# M7106C.net
KiCad netlist of a schematic drawn in EAGLE
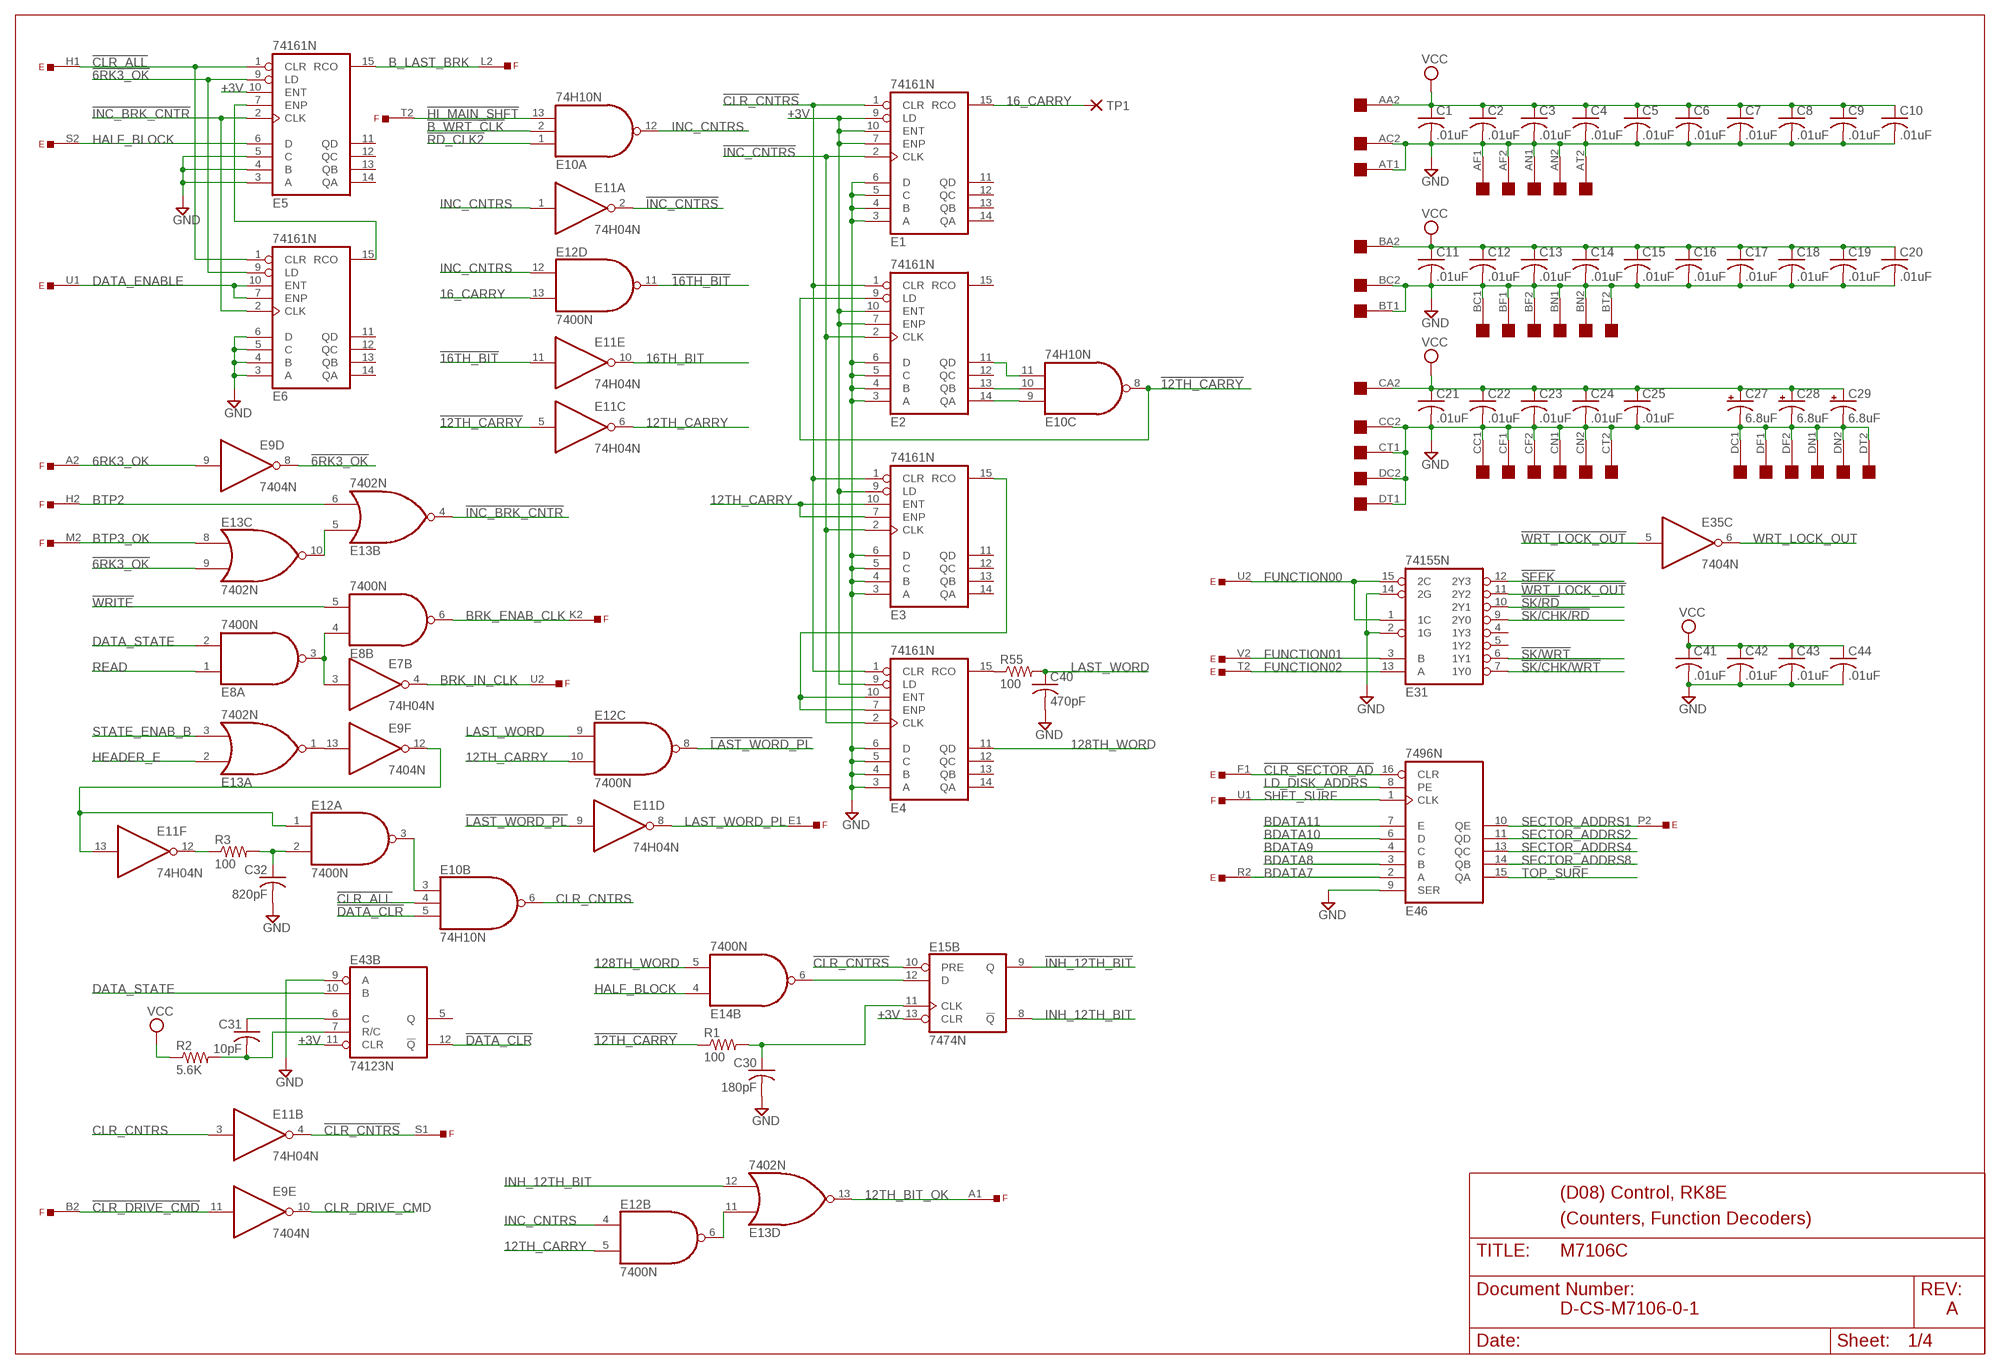
[diagram p0: schematic, sheet 1]
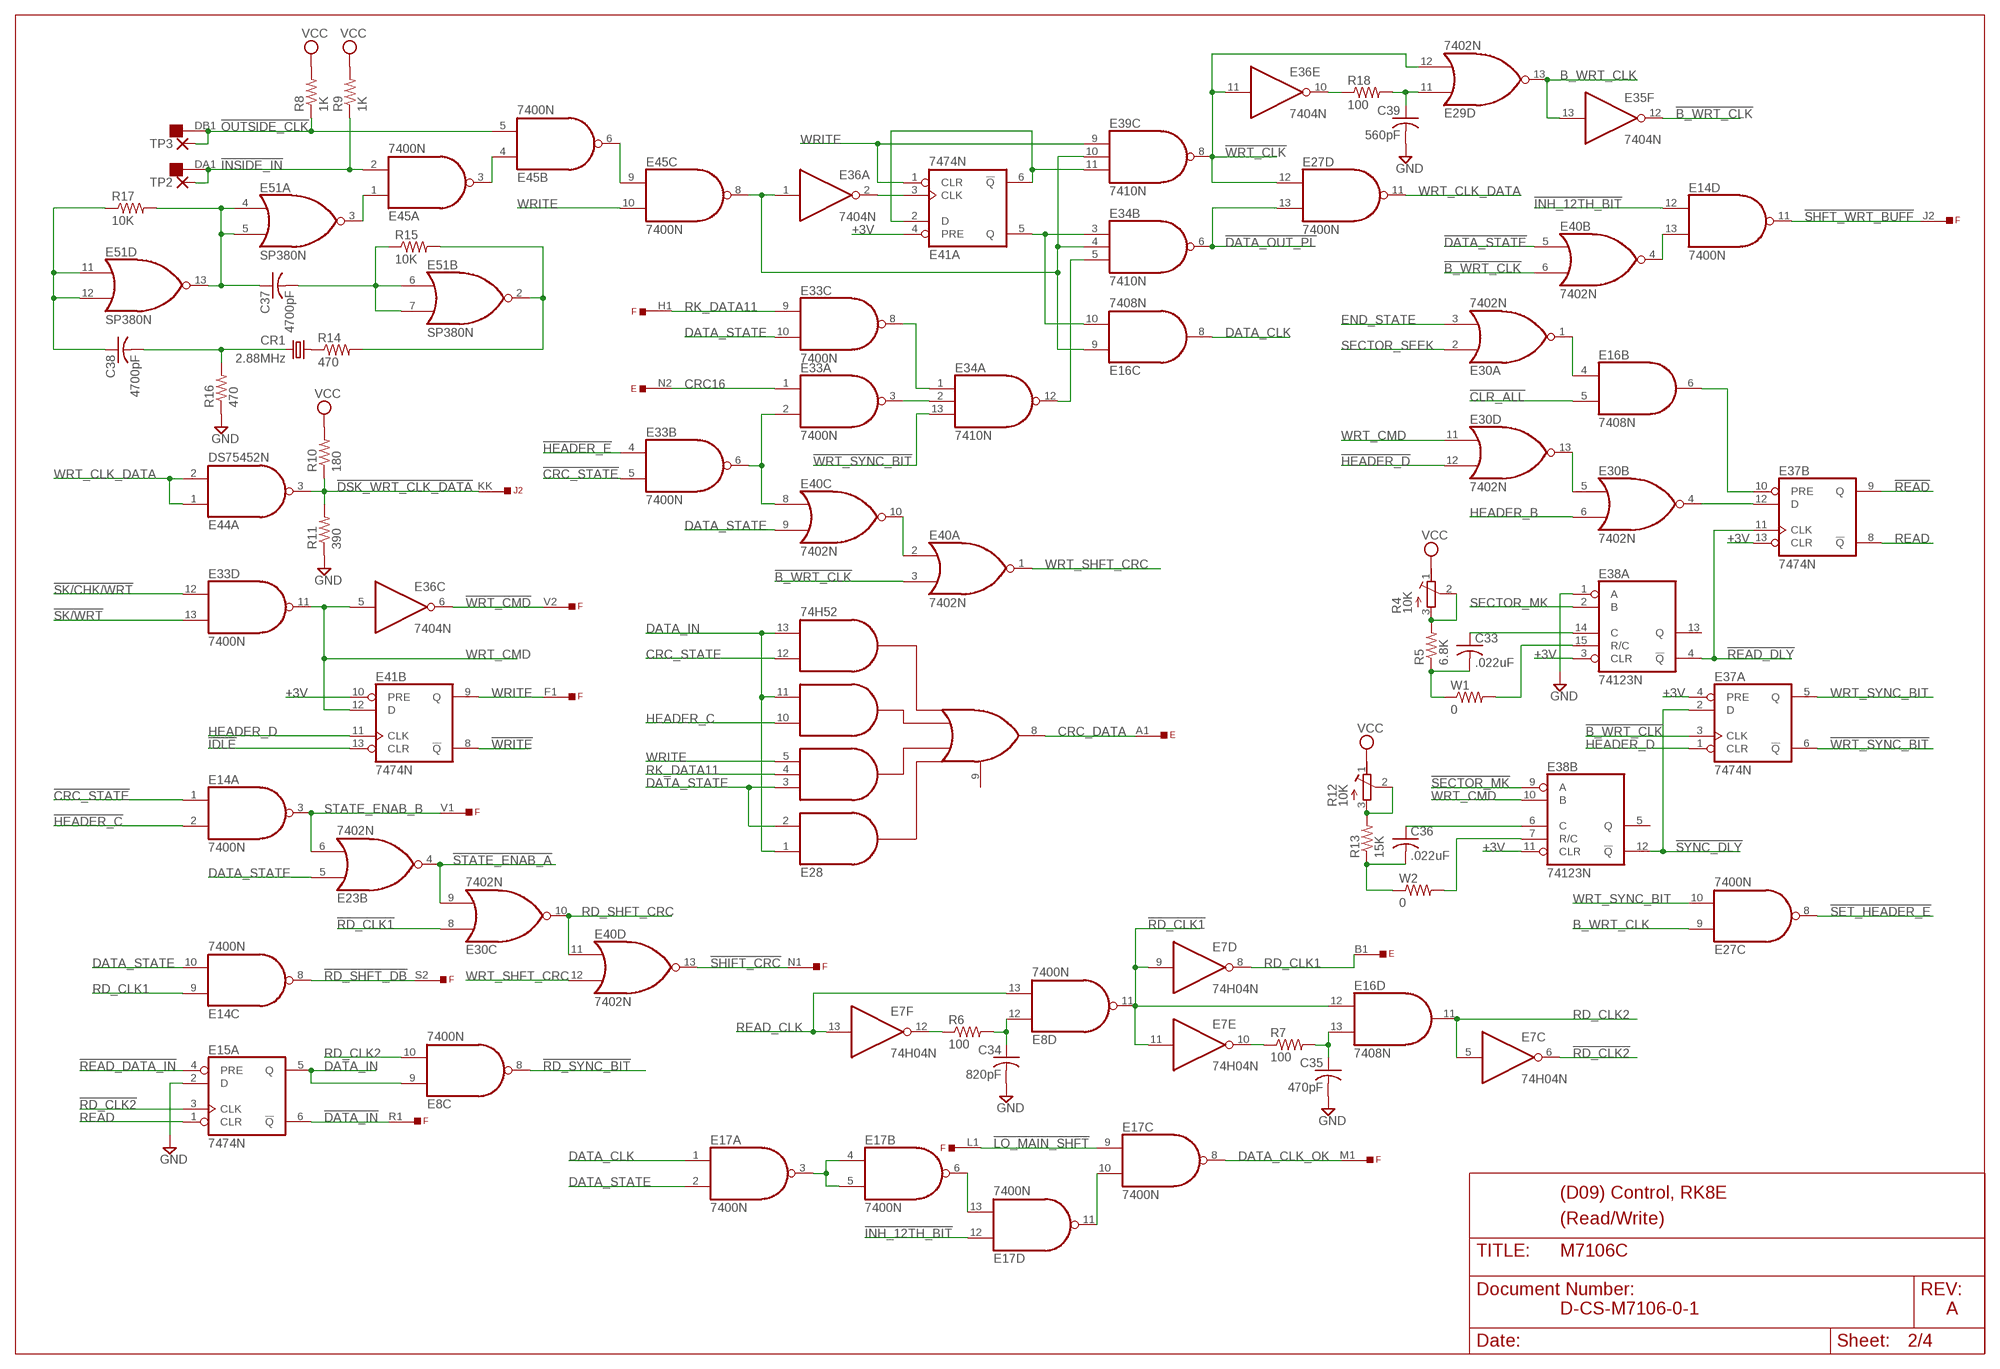
[diagram p1: schematic, sheet 2]
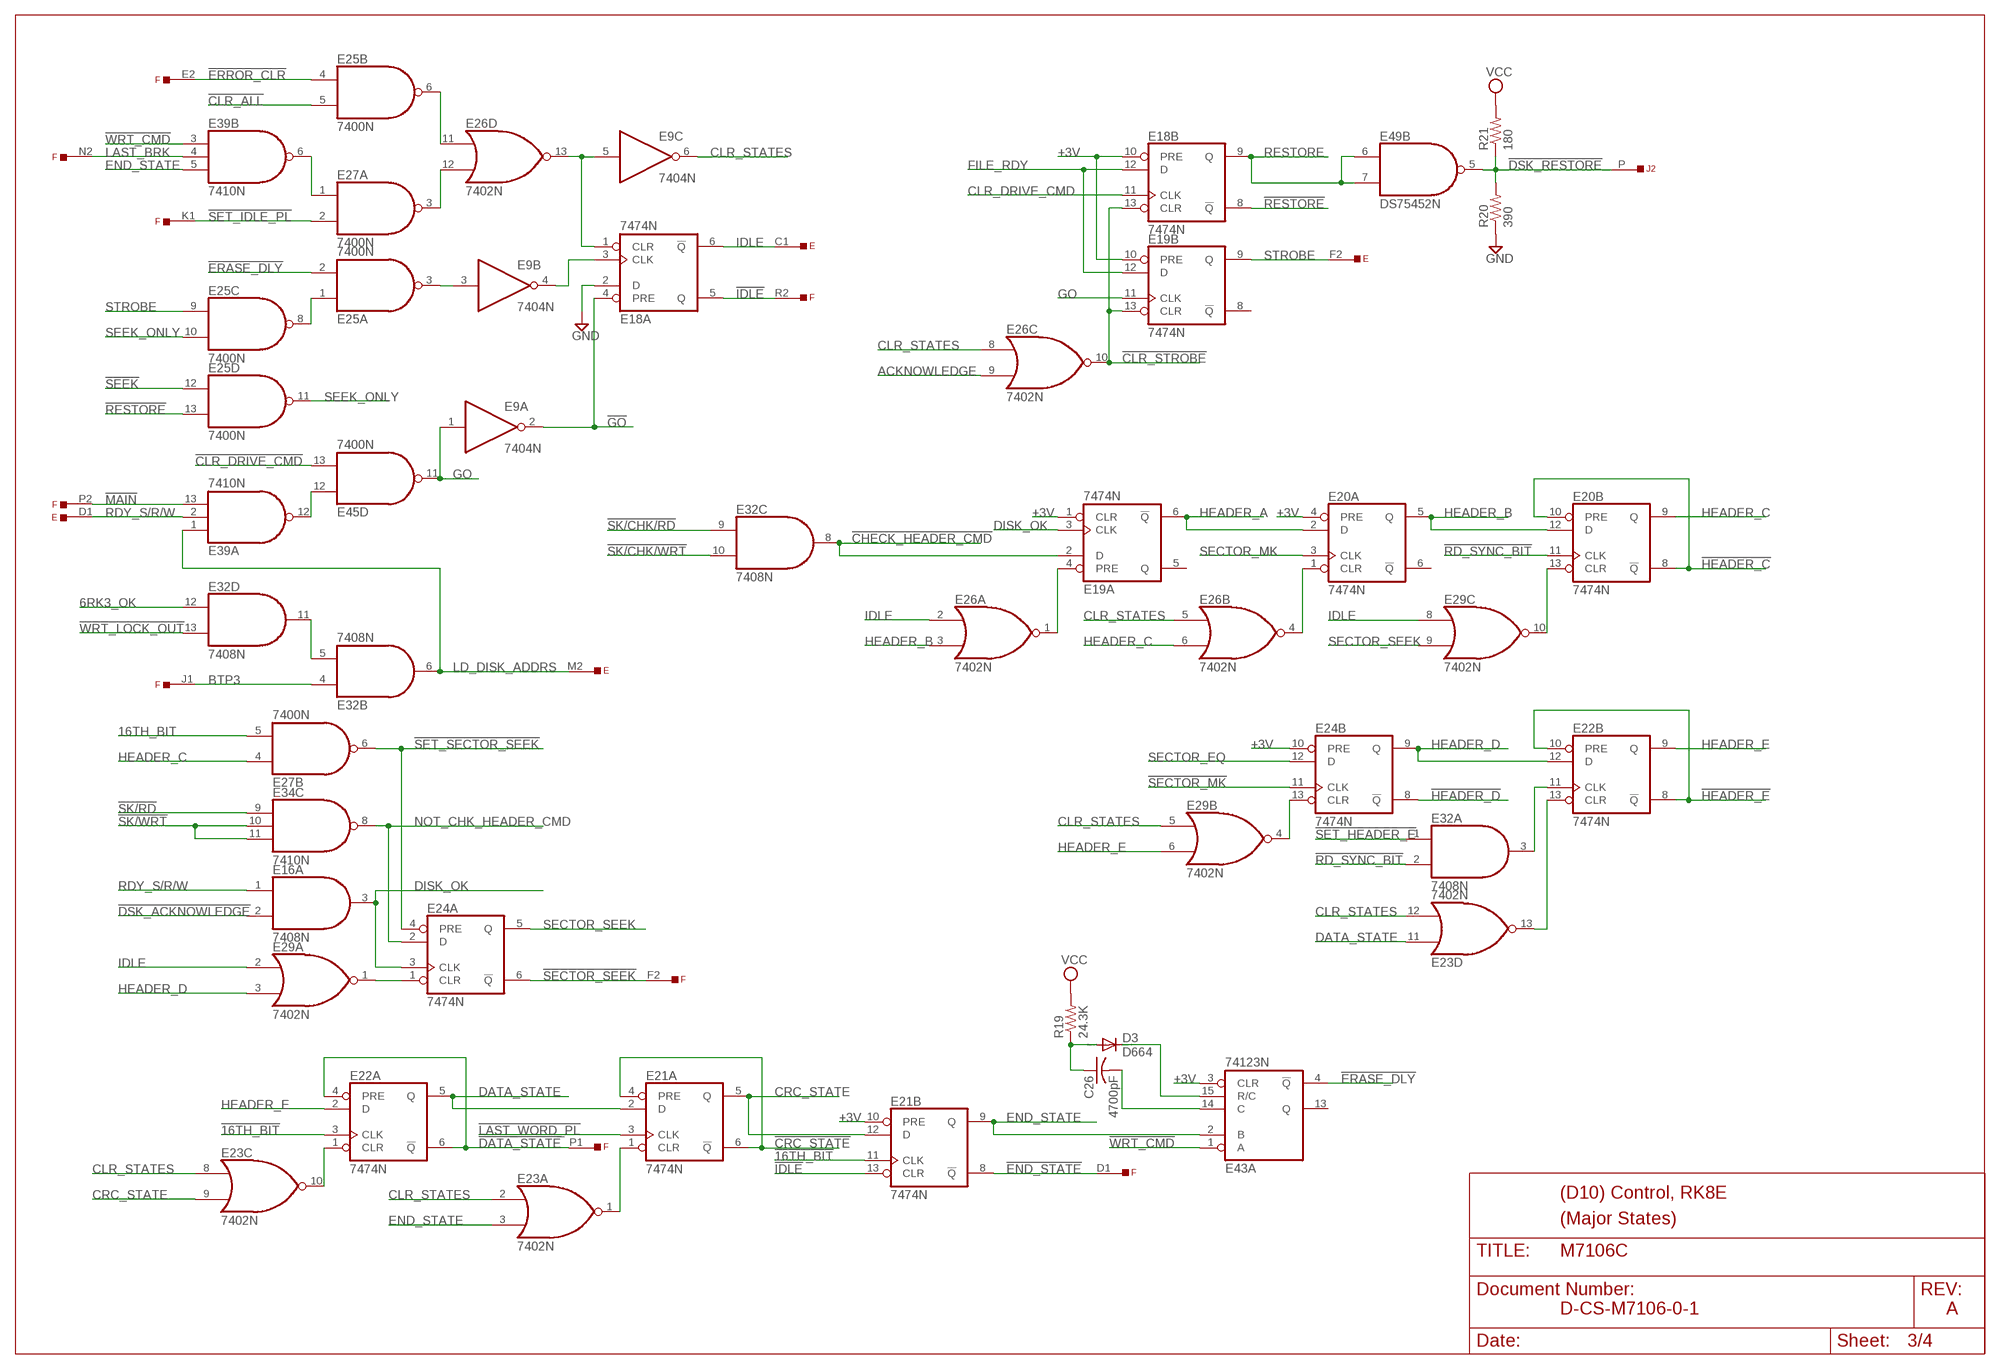
[diagram p2: schematic, sheet 3]
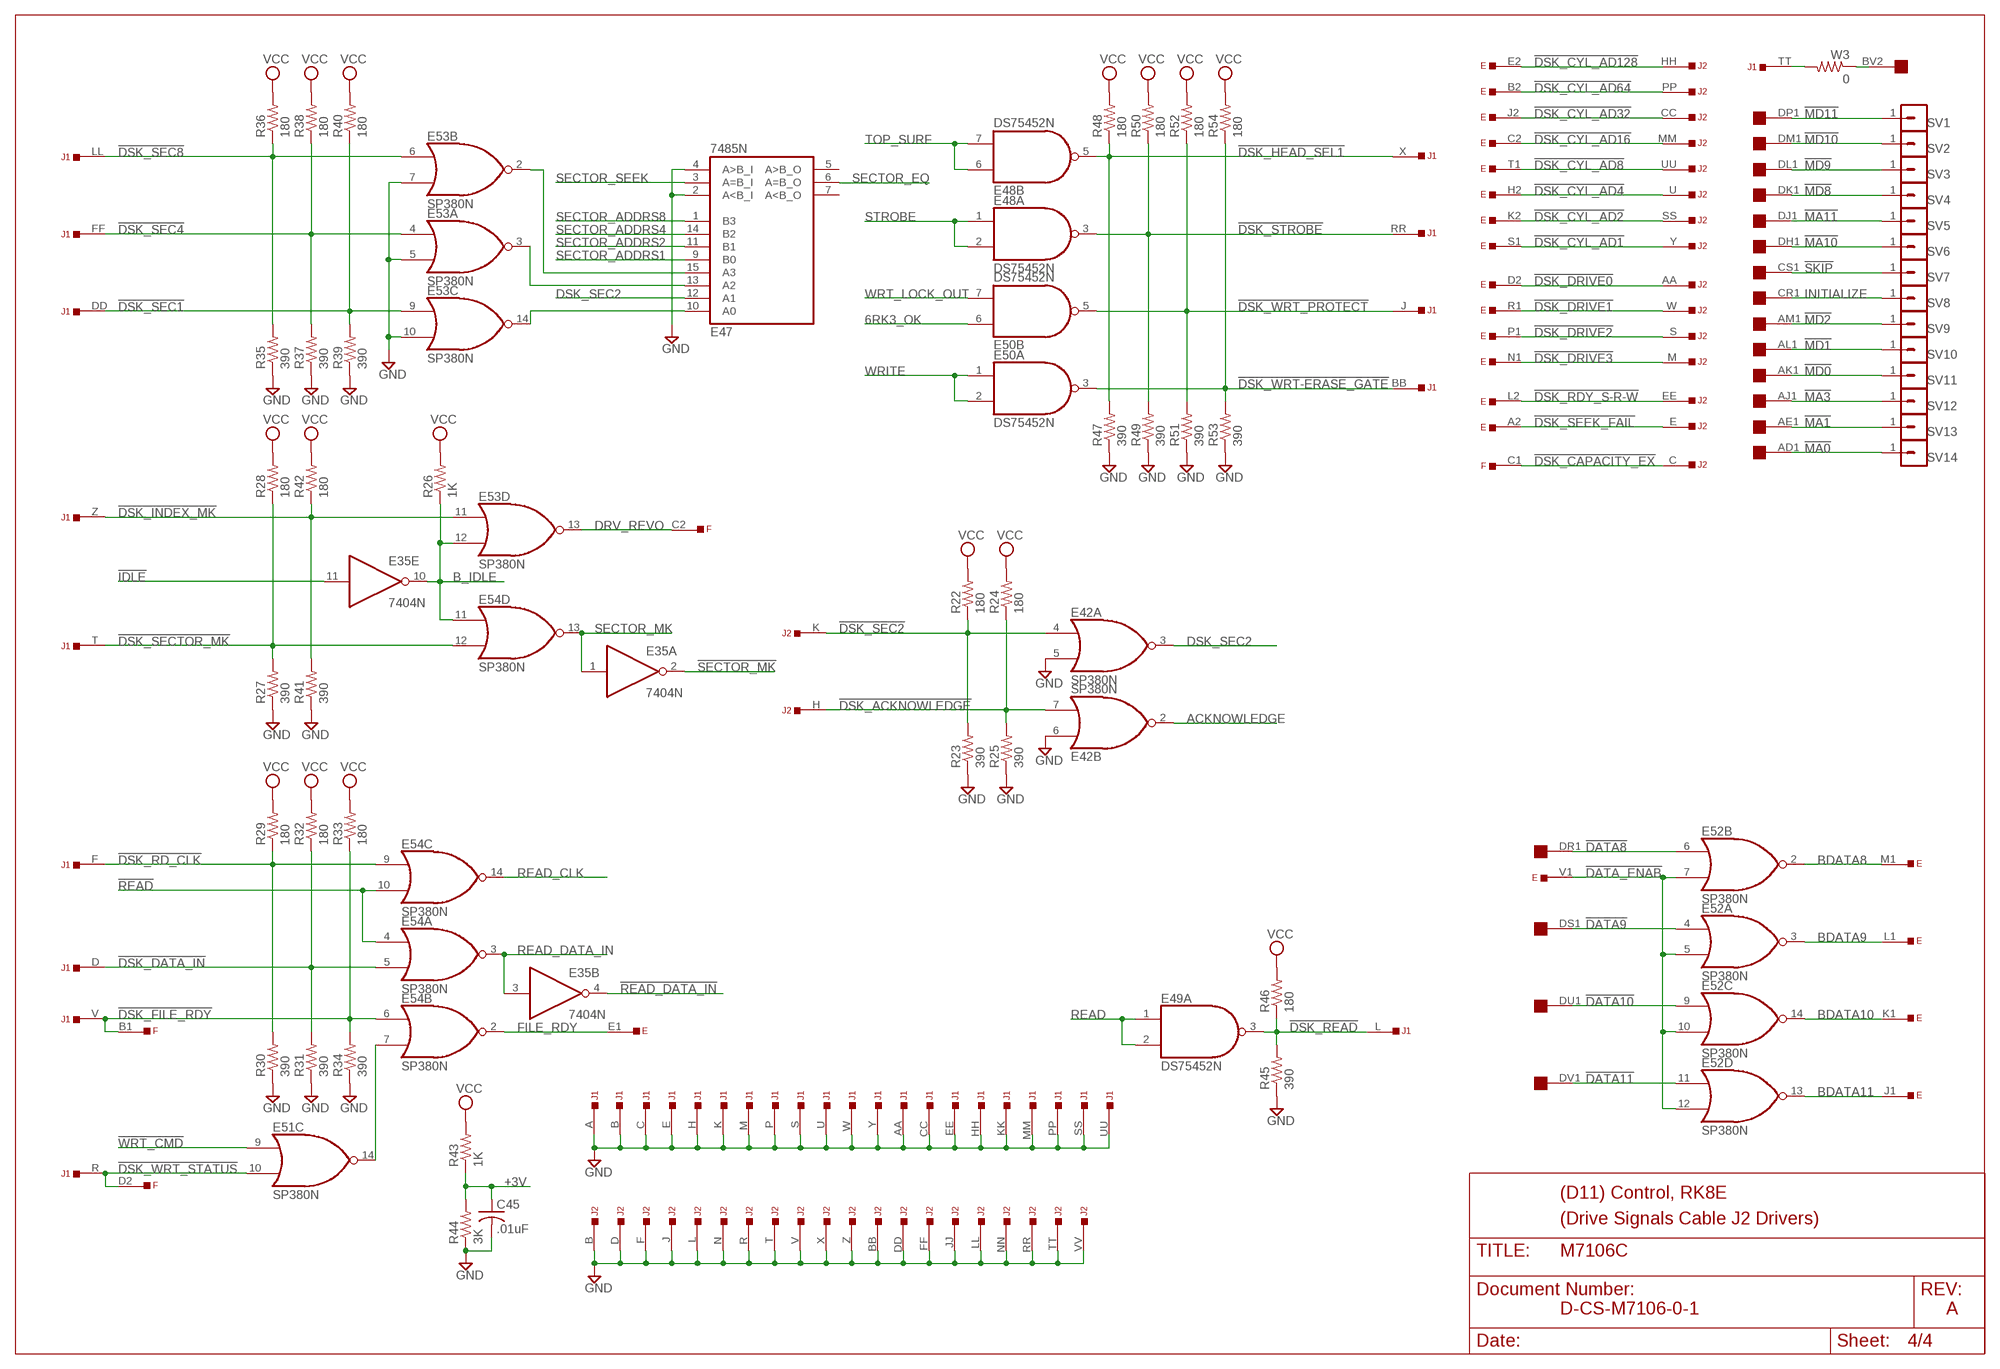
[diagram p3: schematic, sheet 4]

(export (version "E")
  (design (tool "Eeschema 10.0.6"))
  (components
    (comp (ref "C1")
      (value ".01uF")
      (footprint "eagle-import:C063-025X075")
      (libsource (lib "eagle-import") (part "C-US"))
    )
    (comp (ref "C2")
      (value ".01uF")
      (footprint "eagle-import:C063-025X075")
      (libsource (lib "eagle-import") (part "C-US"))
    )
    (comp (ref "C3")
      (value ".01uF")
      (footprint "eagle-import:C063-025X075")
      (libsource (lib "eagle-import") (part "C-US"))
    )
    (comp (ref "C4")
      (value ".01uF")
      (footprint "eagle-import:C063-025X075")
      (libsource (lib "eagle-import") (part "C-US"))
    )
    (comp (ref "C5")
      (value ".01uF")
      (footprint "eagle-import:C063-025X075")
      (libsource (lib "eagle-import") (part "C-US"))
    )
    (comp (ref "C6")
      (value ".01uF")
      (footprint "eagle-import:C063-025X075")
      (libsource (lib "eagle-import") (part "C-US"))
    )
    (comp (ref "C7")
      (value ".01uF")
      (footprint "eagle-import:C063-025X075")
      (libsource (lib "eagle-import") (part "C-US"))
    )
    (comp (ref "C8")
      (value ".01uF")
      (footprint "eagle-import:C063-025X075")
      (libsource (lib "eagle-import") (part "C-US"))
    )
    (comp (ref "C9")
      (value ".01uF")
      (footprint "eagle-import:C063-025X075")
      (libsource (lib "eagle-import") (part "C-US"))
    )
    (comp (ref "C10")
      (value ".01uF")
      (footprint "eagle-import:C063-025X075")
      (libsource (lib "eagle-import") (part "C-US"))
    )
    (comp (ref "C11")
      (value ".01uF")
      (footprint "eagle-import:C063-025X075")
      (libsource (lib "eagle-import") (part "C-US"))
    )
    (comp (ref "C12")
      (value ".01uF")
      (footprint "eagle-import:C063-025X075")
      (libsource (lib "eagle-import") (part "C-US"))
    )
    (comp (ref "C13")
      (value ".01uF")
      (footprint "eagle-import:C063-025X075")
      (libsource (lib "eagle-import") (part "C-US"))
    )
    (comp (ref "C14")
      (value ".01uF")
      (footprint "eagle-import:C063-025X075")
      (libsource (lib "eagle-import") (part "C-US"))
    )
    (comp (ref "C15")
      (value ".01uF")
      (footprint "eagle-import:C063-025X075")
      (libsource (lib "eagle-import") (part "C-US"))
    )
    (comp (ref "C16")
      (value ".01uF")
      (footprint "eagle-import:C063-025X075")
      (libsource (lib "eagle-import") (part "C-US"))
    )
    (comp (ref "C17")
      (value ".01uF")
      (footprint "eagle-import:C063-025X075")
      (libsource (lib "eagle-import") (part "C-US"))
    )
    (comp (ref "C18")
      (value ".01uF")
      (footprint "eagle-import:C063-025X075")
      (libsource (lib "eagle-import") (part "C-US"))
    )
    (comp (ref "C19")
      (value ".01uF")
      (footprint "eagle-import:C063-025X075")
      (libsource (lib "eagle-import") (part "C-US"))
    )
    (comp (ref "C20")
      (value ".01uF")
      (footprint "eagle-import:C063-025X075")
      (libsource (lib "eagle-import") (part "C-US"))
    )
    (comp (ref "C21")
      (value ".01uF")
      (footprint "eagle-import:C063-025X075")
      (libsource (lib "eagle-import") (part "C-US"))
    )
    (comp (ref "C22")
      (value ".01uF")
      (footprint "eagle-import:C063-025X075")
      (libsource (lib "eagle-import") (part "C-US"))
    )
    (comp (ref "C23")
      (value ".01uF")
      (footprint "eagle-import:C063-025X075")
      (libsource (lib "eagle-import") (part "C-US"))
    )
    (comp (ref "C24")
      (value ".01uF")
      (footprint "eagle-import:C063-025X075")
      (libsource (lib "eagle-import") (part "C-US"))
    )
    (comp (ref "C25")
      (value ".01uF")
      (footprint "eagle-import:C063-025X075")
      (libsource (lib "eagle-import") (part "C-US"))
    )
    (comp (ref "C27")
      (value "6.8uF")
      (footprint "eagle-import:E12-8")
      (libsource (lib "eagle-import") (part "CPOL-USE20-8AXIAL"))
    )
    (comp (ref "C28")
      (value "6.8uF")
      (footprint "eagle-import:E12-8")
      (libsource (lib "eagle-import") (part "CPOL-USE20-8AXIAL"))
    )
    (comp (ref "C29")
      (value "6.8uF")
      (footprint "eagle-import:E12-8")
      (libsource (lib "eagle-import") (part "CPOL-USE20-8AXIAL"))
    )
    (comp (ref "C30")
      (value "180pF")
      (footprint "eagle-import:C063-025X075")
      (libsource (lib "eagle-import") (part "C-US"))
    )
    (comp (ref "C31")
      (value "10pF")
      (footprint "eagle-import:C063-025X075")
      (libsource (lib "eagle-import") (part "C-US"))
    )
    (comp (ref "C32")
      (value "820pF")
      (footprint "eagle-import:C063-025X075")
      (libsource (lib "eagle-import") (part "C-US"))
    )
    (comp (ref "C40")
      (value "470pF")
      (footprint "eagle-import:C063-025X075")
      (libsource (lib "eagle-import") (part "C-US"))
    )
    (comp (ref "C41")
      (value ".01uF")
      (footprint "eagle-import:C063-025X075")
      (libsource (lib "eagle-import") (part "C-US"))
    )
    (comp (ref "C42")
      (value ".01uF")
      (footprint "eagle-import:C063-025X075")
      (libsource (lib "eagle-import") (part "C-US"))
    )
    (comp (ref "C43")
      (value ".01uF")
      (footprint "eagle-import:C063-025X075")
      (libsource (lib "eagle-import") (part "C-US"))
    )
    (comp (ref "C44")
      (value ".01uF")
      (footprint "eagle-import:C063-025X075")
      (libsource (lib "eagle-import") (part "C-US"))
    )
    (comp (ref "E")
      (value "EDGE-TOP")
      (footprint "eagle-import:EDGE-CON2")
      (libsource (lib "eagle-import") (part "EDGE-TOP"))
    )
    (comp (ref "E1")
      (value "74161N")
      (footprint "eagle-import:DIL16")
      (libsource (lib "eagle-import") (part "74161N"))
    )
    (comp (ref "E2")
      (value "74161N")
      (footprint "eagle-import:DIL16")
      (libsource (lib "eagle-import") (part "74161N"))
    )
    (comp (ref "E3")
      (value "74161N")
      (footprint "eagle-import:DIL16")
      (libsource (lib "eagle-import") (part "74161N"))
    )
    (comp (ref "E4")
      (value "74161N")
      (footprint "eagle-import:DIL16")
      (libsource (lib "eagle-import") (part "74161N"))
    )
    (comp (ref "E5")
      (value "74161N")
      (footprint "eagle-import:DIL16")
      (libsource (lib "eagle-import") (part "74161N"))
    )
    (comp (ref "E6")
      (value "74161N")
      (footprint "eagle-import:DIL16")
      (libsource (lib "eagle-import") (part "74161N"))
    )
    (comp (ref "E7")
      (value "74H04N")
      (footprint "eagle-import:DIL14")
      (libsource (lib "eagle-import") (part "7404N"))
    )
    (comp (ref "E8")
      (value "7400N")
      (footprint "eagle-import:DIL14")
      (libsource (lib "eagle-import") (part "7400N"))
    )
    (comp (ref "E9")
      (value "7404N")
      (footprint "eagle-import:DIL14")
      (libsource (lib "eagle-import") (part "7404N"))
    )
    (comp (ref "E10")
      (value "74H10N")
      (footprint "eagle-import:DIL14")
      (libsource (lib "eagle-import") (part "7410N"))
    )
    (comp (ref "E11")
      (value "74H04N")
      (footprint "eagle-import:DIL14")
      (libsource (lib "eagle-import") (part "7404N"))
    )
    (comp (ref "E12")
      (value "7400N")
      (footprint "eagle-import:DIL14")
      (libsource (lib "eagle-import") (part "7400N"))
    )
    (comp (ref "E13")
      (value "7402N")
      (footprint "eagle-import:DIL14")
      (libsource (lib "eagle-import") (part "7402N"))
    )
    (comp (ref "E14")
      (value "7400N")
      (footprint "eagle-import:DIL14")
      (libsource (lib "eagle-import") (part "7400N"))
    )
    (comp (ref "E15")
      (value "7474N")
      (footprint "eagle-import:DIL14")
      (libsource (lib "eagle-import") (part "7474NS"))
    )
    (comp (ref "E31")
      (value "74155N")
      (footprint "eagle-import:DIL16")
      (libsource (lib "eagle-import") (part "74155N"))
    )
    (comp (ref "E35")
      (value "7404N")
      (footprint "eagle-import:DIL14")
      (libsource (lib "eagle-import") (part "7404N"))
    )
    (comp (ref "E43")
      (value "74123N")
      (footprint "eagle-import:DIL16")
      (libsource (lib "eagle-import") (part "74123N"))
    )
    (comp (ref "E46")
      (value "7496N")
      (footprint "eagle-import:DIL16")
      (libsource (lib "eagle-import") (part "7496NLS"))
    )
    (comp (ref "F")
      (value "EDGE-TOP")
      (footprint "eagle-import:EDGE-CON2")
      (libsource (lib "eagle-import") (part "EDGE-TOP"))
    )
    (comp (ref "OMNIBUS")
      (value "QUAD")
      (footprint "eagle-import:EDGE-CON8")
      (libsource (lib "eagle-import") (part "QUAD"))
    )
    (comp (ref "R1")
      (value "100")
      (footprint "eagle-import:0207_10")
      (libsource (lib "eagle-import") (part "R-US_0207/10"))
    )
    (comp (ref "R2")
      (value "5.6K")
      (footprint "eagle-import:0207_10")
      (libsource (lib "eagle-import") (part "R-US_0207/10"))
    )
    (comp (ref "R3")
      (value "100")
      (footprint "eagle-import:0207_10")
      (libsource (lib "eagle-import") (part "R-US_0207/10"))
    )
    (comp (ref "R55")
      (value "100")
      (footprint "eagle-import:0207_10")
      (libsource (lib "eagle-import") (part "R-US_0207/10"))
    )
    (comp (ref "TP1")
      (value "PAD-0420")
      (footprint "eagle-import:0420")
      (libsource (lib "eagle-import") (part "PAD-0420"))
    )
    (comp (ref "C33")
      (value ".022uF")
      (footprint "eagle-import:C203-054-229")
      (libsource (lib "eagle-import") (part "C-US8"))
    )
    (comp (ref "C34")
      (value "820pF")
      (footprint "eagle-import:C063-025X075")
      (libsource (lib "eagle-import") (part "C-US"))
    )
    (comp (ref "C35")
      (value "470pF")
      (footprint "eagle-import:C063-025X075")
      (libsource (lib "eagle-import") (part "C-US"))
    )
    (comp (ref "C36")
      (value ".022uF")
      (footprint "eagle-import:C203-054-229")
      (libsource (lib "eagle-import") (part "C-US8"))
    )
    (comp (ref "C37")
      (value "4700pF")
      (footprint "eagle-import:C203-054-229")
      (libsource (lib "eagle-import") (part "C-US8"))
    )
    (comp (ref "C38")
      (value "4700pF")
      (footprint "eagle-import:C203-054-229")
      (libsource (lib "eagle-import") (part "C-US8"))
    )
    (comp (ref "C39")
      (value "560pF")
      (footprint "eagle-import:C063-025X075")
      (libsource (lib "eagle-import") (part "C-US"))
    )
    (comp (ref "CR1")
      (value "2.88MHz")
      (footprint "eagle-import:HC49TL-H")
      (libsource (lib "eagle-import") (part "CRYSTALHC49TL-H"))
    )
    (comp (ref "E16")
      (value "7408N")
      (footprint "eagle-import:DIL14")
      (libsource (lib "eagle-import") (part "7408NS"))
    )
    (comp (ref "E17")
      (value "7400N")
      (footprint "eagle-import:DIL14")
      (libsource (lib "eagle-import") (part "7400N"))
    )
    (comp (ref "E23")
      (value "7402N")
      (footprint "eagle-import:DIL14")
      (libsource (lib "eagle-import") (part "7402N"))
    )
    (comp (ref "E27")
      (value "7400N")
      (footprint "eagle-import:DIL14")
      (libsource (lib "eagle-import") (part "7400N"))
    )
    (comp (ref "E28")
      (value "74H52")
      (footprint "eagle-import:DIL14")
      (libsource (lib "eagle-import") (part "7452H"))
    )
    (comp (ref "E29")
      (value "7402N")
      (footprint "eagle-import:DIL14")
      (libsource (lib "eagle-import") (part "7402N"))
    )
    (comp (ref "E30")
      (value "7402N")
      (footprint "eagle-import:DIL14")
      (libsource (lib "eagle-import") (part "7402N"))
    )
    (comp (ref "E33")
      (value "7400N")
      (footprint "eagle-import:DIL14")
      (libsource (lib "eagle-import") (part "7400N"))
    )
    (comp (ref "E34")
      (value "7410N")
      (footprint "eagle-import:DIL14")
      (libsource (lib "eagle-import") (part "7410N"))
    )
    (comp (ref "E36")
      (value "7404N")
      (footprint "eagle-import:DIL14")
      (libsource (lib "eagle-import") (part "7404N"))
    )
    (comp (ref "E37")
      (value "7474N")
      (footprint "eagle-import:DIL14")
      (libsource (lib "eagle-import") (part "7474NS"))
    )
    (comp (ref "E38")
      (value "74123N")
      (footprint "eagle-import:DIL16")
      (libsource (lib "eagle-import") (part "74123N"))
    )
    (comp (ref "E39")
      (value "7410N")
      (footprint "eagle-import:DIL14")
      (libsource (lib "eagle-import") (part "7410N"))
    )
    (comp (ref "E40")
      (value "7402N")
      (footprint "eagle-import:DIL14")
      (libsource (lib "eagle-import") (part "7402N"))
    )
    (comp (ref "E41")
      (value "7474N")
      (footprint "eagle-import:DIL14")
      (libsource (lib "eagle-import") (part "7474NS"))
    )
    (comp (ref "E44")
      (value "DS75452N")
      (footprint "eagle-import:DIL08")
      (libsource (lib "eagle-import") (part "DS75452N"))
    )
    (comp (ref "E45")
      (value "7400N")
      (footprint "eagle-import:DIL14")
      (libsource (lib "eagle-import") (part "7400N"))
    )
    (comp (ref "E51")
      (value "SP380N")
      (footprint "eagle-import:DIL14")
      (libsource (lib "eagle-import") (part "SP380N"))
    )
    (comp (ref "J2")
      (value "DEC40PINSH")
      (footprint "eagle-import:DEC40PINH")
      (libsource (lib "eagle-import") (part "DEC40PINSH"))
    )
    (comp (ref "R4")
      (value "10K")
      (footprint "eagle-import:3006Y")
      (libsource (lib "eagle-import") (part "275P"))
    )
    (comp (ref "R5")
      (value "6.8K")
      (footprint "eagle-import:0207_10")
      (libsource (lib "eagle-import") (part "R-US_0207/10"))
    )
    (comp (ref "R6")
      (value "100")
      (footprint "eagle-import:0207_10")
      (libsource (lib "eagle-import") (part "R-US_0207/10"))
    )
    (comp (ref "R7")
      (value "100")
      (footprint "eagle-import:0207_10")
      (libsource (lib "eagle-import") (part "R-US_0207/10"))
    )
    (comp (ref "R8")
      (value "1K")
      (footprint "eagle-import:0207_10")
      (libsource (lib "eagle-import") (part "R-US_0207/10"))
    )
    (comp (ref "R9")
      (value "1K")
      (footprint "eagle-import:0207_10")
      (libsource (lib "eagle-import") (part "R-US_0207/10"))
    )
    (comp (ref "R10")
      (value "180")
      (footprint "eagle-import:0207_10")
      (libsource (lib "eagle-import") (part "R-US_0207/10"))
    )
    (comp (ref "R11")
      (value "390")
      (footprint "eagle-import:0207_10")
      (libsource (lib "eagle-import") (part "R-US_0207/10"))
    )
    (comp (ref "R12")
      (value "10K")
      (footprint "eagle-import:3006Y")
      (libsource (lib "eagle-import") (part "275P"))
    )
    (comp (ref "R13")
      (value "15K")
      (footprint "eagle-import:0207_10")
      (libsource (lib "eagle-import") (part "R-US_0207/10"))
    )
    (comp (ref "R14")
      (value "470")
      (footprint "eagle-import:0207_10")
      (libsource (lib "eagle-import") (part "R-US_0207/10"))
    )
    (comp (ref "R15")
      (value "10K")
      (footprint "eagle-import:0207_10")
      (libsource (lib "eagle-import") (part "R-US_0207/10"))
    )
    (comp (ref "R16")
      (value "470")
      (footprint "eagle-import:0207_10")
      (libsource (lib "eagle-import") (part "R-US_0207/10"))
    )
    (comp (ref "R17")
      (value "10K")
      (footprint "eagle-import:0207_10")
      (libsource (lib "eagle-import") (part "R-US_0207/10"))
    )
    (comp (ref "R18")
      (value "100")
      (footprint "eagle-import:0207_10")
      (libsource (lib "eagle-import") (part "R-US_0207/10"))
    )
    (comp (ref "TP2")
      (value "PAD-0420")
      (footprint "eagle-import:0420")
      (libsource (lib "eagle-import") (part "PAD-0420"))
    )
    (comp (ref "TP3")
      (value "PAD-0420")
      (footprint "eagle-import:0420")
      (libsource (lib "eagle-import") (part "PAD-0420"))
    )
    (comp (ref "W1")
      (value "0")
      (footprint "eagle-import:0207_10")
      (libsource (lib "eagle-import") (part "R-US_0207/10"))
    )
    (comp (ref "W2")
      (value "0")
      (footprint "eagle-import:0207_10")
      (libsource (lib "eagle-import") (part "R-US_0207/10"))
    )
    (comp (ref "C45")
      (value ".01uF")
      (footprint "eagle-import:C063-025X075")
      (libsource (lib "eagle-import") (part "C-US"))
    )
    (comp (ref "E42")
      (value "SP380N")
      (footprint "eagle-import:DIL14")
      (libsource (lib "eagle-import") (part "SP380N"))
    )
    (comp (ref "E47")
      (value "7485N")
      (footprint "eagle-import:DIL16")
      (libsource (lib "eagle-import") (part "7485N"))
    )
    (comp (ref "E48")
      (value "DS75452N")
      (footprint "eagle-import:DIL08")
      (libsource (lib "eagle-import") (part "DS75452N"))
    )
    (comp (ref "E49")
      (value "DS75452N")
      (footprint "eagle-import:DIL08")
      (libsource (lib "eagle-import") (part "DS75452N"))
    )
    (comp (ref "E50")
      (value "DS75452N")
      (footprint "eagle-import:DIL08")
      (libsource (lib "eagle-import") (part "DS75452N"))
    )
    (comp (ref "E52")
      (value "SP380N")
      (footprint "eagle-import:DIL14")
      (libsource (lib "eagle-import") (part "SP380N"))
    )
    (comp (ref "E53")
      (value "SP380N")
      (footprint "eagle-import:DIL14")
      (libsource (lib "eagle-import") (part "SP380N"))
    )
    (comp (ref "E54")
      (value "SP380N")
      (footprint "eagle-import:DIL14")
      (libsource (lib "eagle-import") (part "SP380N"))
    )
    (comp (ref "J1")
      (value "DEC40PINSH")
      (footprint "eagle-import:DEC40PINH")
      (libsource (lib "eagle-import") (part "DEC40PINSH"))
    )
    (comp (ref "R22")
      (value "180")
      (footprint "eagle-import:0207_10")
      (libsource (lib "eagle-import") (part "R-US_0207/10"))
    )
    (comp (ref "R23")
      (value "390")
      (footprint "eagle-import:0207_10")
      (libsource (lib "eagle-import") (part "R-US_0207/10"))
    )
    (comp (ref "R24")
      (value "180")
      (footprint "eagle-import:0207_10")
      (libsource (lib "eagle-import") (part "R-US_0207/10"))
    )
    (comp (ref "R25")
      (value "390")
      (footprint "eagle-import:0207_10")
      (libsource (lib "eagle-import") (part "R-US_0207/10"))
    )
    (comp (ref "R26")
      (value "1K")
      (footprint "eagle-import:0207_10")
      (libsource (lib "eagle-import") (part "R-US_0207/10"))
    )
    (comp (ref "R27")
      (value "390")
      (footprint "eagle-import:0207_10")
      (libsource (lib "eagle-import") (part "R-US_0207/10"))
    )
    (comp (ref "R28")
      (value "180")
      (footprint "eagle-import:0207_10")
      (libsource (lib "eagle-import") (part "R-US_0207/10"))
    )
    (comp (ref "R29")
      (value "180")
      (footprint "eagle-import:0207_10")
      (libsource (lib "eagle-import") (part "R-US_0207/10"))
    )
    (comp (ref "R30")
      (value "390")
      (footprint "eagle-import:0207_10")
      (libsource (lib "eagle-import") (part "R-US_0207/10"))
    )
    (comp (ref "R31")
      (value "390")
      (footprint "eagle-import:0207_10")
      (libsource (lib "eagle-import") (part "R-US_0207/10"))
    )
    (comp (ref "R32")
      (value "180")
      (footprint "eagle-import:0207_10")
      (libsource (lib "eagle-import") (part "R-US_0207/10"))
    )
    (comp (ref "R33")
      (value "180")
      (footprint "eagle-import:0207_10")
      (libsource (lib "eagle-import") (part "R-US_0207/10"))
    )
    (comp (ref "R34")
      (value "390")
      (footprint "eagle-import:0207_10")
      (libsource (lib "eagle-import") (part "R-US_0207/10"))
    )
    (comp (ref "R35")
      (value "390")
      (footprint "eagle-import:0207_10")
      (libsource (lib "eagle-import") (part "R-US_0207/10"))
    )
    (comp (ref "R36")
      (value "180")
      (footprint "eagle-import:0207_10")
      (libsource (lib "eagle-import") (part "R-US_0207/10"))
    )
    (comp (ref "R37")
      (value "390")
      (footprint "eagle-import:0207_10")
      (libsource (lib "eagle-import") (part "R-US_0207/10"))
    )
    (comp (ref "R38")
      (value "180")
      (footprint "eagle-import:0207_10")
      (libsource (lib "eagle-import") (part "R-US_0207/10"))
    )
    (comp (ref "R39")
      (value "390")
      (footprint "eagle-import:0207_10")
      (libsource (lib "eagle-import") (part "R-US_0207/10"))
    )
    (comp (ref "R40")
      (value "180")
      (footprint "eagle-import:0207_10")
      (libsource (lib "eagle-import") (part "R-US_0207/10"))
    )
    (comp (ref "R41")
      (value "390")
      (footprint "eagle-import:0207_10")
      (libsource (lib "eagle-import") (part "R-US_0207/10"))
    )
    (comp (ref "R42")
      (value "180")
      (footprint "eagle-import:0207_10")
      (libsource (lib "eagle-import") (part "R-US_0207/10"))
    )
    (comp (ref "R43")
      (value "1K")
      (footprint "eagle-import:0207_10")
      (libsource (lib "eagle-import") (part "R-US_0207/10"))
    )
    (comp (ref "R44")
      (value "3K")
      (footprint "eagle-import:0207_10")
      (libsource (lib "eagle-import") (part "R-US_0207/10"))
    )
    (comp (ref "R45")
      (value "390")
      (footprint "eagle-import:0207_10")
      (libsource (lib "eagle-import") (part "R-US_0207/10"))
    )
    (comp (ref "R46")
      (value "180")
      (footprint "eagle-import:0207_10")
      (libsource (lib "eagle-import") (part "R-US_0207/10"))
    )
    (comp (ref "R47")
      (value "390")
      (footprint "eagle-import:0207_10")
      (libsource (lib "eagle-import") (part "R-US_0207/10"))
    )
    (comp (ref "R48")
      (value "180")
      (footprint "eagle-import:0207_10")
      (libsource (lib "eagle-import") (part "R-US_0207/10"))
    )
    (comp (ref "R49")
      (value "390")
      (footprint "eagle-import:0207_10")
      (libsource (lib "eagle-import") (part "R-US_0207/10"))
    )
    (comp (ref "R50")
      (value "180")
      (footprint "eagle-import:0207_10")
      (libsource (lib "eagle-import") (part "R-US_0207/10"))
    )
    (comp (ref "R51")
      (value "390")
      (footprint "eagle-import:0207_10")
      (libsource (lib "eagle-import") (part "R-US_0207/10"))
    )
    (comp (ref "R52")
      (value "180")
      (footprint "eagle-import:0207_10")
      (libsource (lib "eagle-import") (part "R-US_0207/10"))
    )
    (comp (ref "R53")
      (value "390")
      (footprint "eagle-import:0207_10")
      (libsource (lib "eagle-import") (part "R-US_0207/10"))
    )
    (comp (ref "R54")
      (value "180")
      (footprint "eagle-import:0207_10")
      (libsource (lib "eagle-import") (part "R-US_0207/10"))
    )
    (comp (ref "SV1")
      (value "MA01-1")
      (footprint "eagle-import:MA01-1")
      (libsource (lib "eagle-import") (part "MA01-1"))
    )
    (comp (ref "SV2")
      (value "MA01-1")
      (footprint "eagle-import:MA01-1")
      (libsource (lib "eagle-import") (part "MA01-1"))
    )
    (comp (ref "SV3")
      (value "MA01-1")
      (footprint "eagle-import:MA01-1")
      (libsource (lib "eagle-import") (part "MA01-1"))
    )
    (comp (ref "SV4")
      (value "MA01-1")
      (footprint "eagle-import:MA01-1")
      (libsource (lib "eagle-import") (part "MA01-1"))
    )
    (comp (ref "SV5")
      (value "MA01-1")
      (footprint "eagle-import:MA01-1")
      (libsource (lib "eagle-import") (part "MA01-1"))
    )
    (comp (ref "SV6")
      (value "MA01-1")
      (footprint "eagle-import:MA01-1")
      (libsource (lib "eagle-import") (part "MA01-1"))
    )
    (comp (ref "SV7")
      (value "MA01-1")
      (footprint "eagle-import:MA01-1")
      (libsource (lib "eagle-import") (part "MA01-1"))
    )
    (comp (ref "SV8")
      (value "MA01-1")
      (footprint "eagle-import:MA01-1")
      (libsource (lib "eagle-import") (part "MA01-1"))
    )
    (comp (ref "SV9")
      (value "MA01-1")
      (footprint "eagle-import:MA01-1")
      (libsource (lib "eagle-import") (part "MA01-1"))
    )
    (comp (ref "SV10")
      (value "MA01-1")
      (footprint "eagle-import:MA01-1")
      (libsource (lib "eagle-import") (part "MA01-1"))
    )
    (comp (ref "SV11")
      (value "MA01-1")
      (footprint "eagle-import:MA01-1")
      (libsource (lib "eagle-import") (part "MA01-1"))
    )
    (comp (ref "SV12")
      (value "MA01-1")
      (footprint "eagle-import:MA01-1")
      (libsource (lib "eagle-import") (part "MA01-1"))
    )
    (comp (ref "SV13")
      (value "MA01-1")
      (footprint "eagle-import:MA01-1")
      (libsource (lib "eagle-import") (part "MA01-1"))
    )
    (comp (ref "SV14")
      (value "MA01-1")
      (footprint "eagle-import:MA01-1")
      (libsource (lib "eagle-import") (part "MA01-1"))
    )
    (comp (ref "W3")
      (value "0")
      (footprint "eagle-import:0207_10")
      (libsource (lib "eagle-import") (part "R-US_0207/10"))
    )
    (comp (ref "C26")
      (value "4700pF")
      (footprint "eagle-import:C203-054-229")
      (libsource (lib "eagle-import") (part "C-US8"))
    )
    (comp (ref "D3")
      (value "D664")
      (footprint "eagle-import:DO35-10")
      (libsource (lib "eagle-import") (part "DIODE-DO35-10"))
    )
    (comp (ref "E18")
      (value "7474N")
      (footprint "eagle-import:DIL14")
      (libsource (lib "eagle-import") (part "7474NS"))
    )
    (comp (ref "E19")
      (value "7474N")
      (footprint "eagle-import:DIL14")
      (libsource (lib "eagle-import") (part "7474NS"))
    )
    (comp (ref "E20")
      (value "7474N")
      (footprint "eagle-import:DIL14")
      (libsource (lib "eagle-import") (part "7474NS"))
    )
    (comp (ref "E21")
      (value "7474N")
      (footprint "eagle-import:DIL14")
      (libsource (lib "eagle-import") (part "7474NS"))
    )
    (comp (ref "E22")
      (value "7474N")
      (footprint "eagle-import:DIL14")
      (libsource (lib "eagle-import") (part "7474NS"))
    )
    (comp (ref "E24")
      (value "7474N")
      (footprint "eagle-import:DIL14")
      (libsource (lib "eagle-import") (part "7474NS"))
    )
    (comp (ref "E25")
      (value "7400N")
      (footprint "eagle-import:DIL14")
      (libsource (lib "eagle-import") (part "7400NS"))
    )
    (comp (ref "E26")
      (value "7402N")
      (footprint "eagle-import:DIL14")
      (libsource (lib "eagle-import") (part "7402N"))
    )
    (comp (ref "E32")
      (value "7408N")
      (footprint "eagle-import:DIL14")
      (libsource (lib "eagle-import") (part "7408NS"))
    )
    (comp (ref "R19")
      (value "24.3K")
      (footprint "eagle-import:0207_15")
      (libsource (lib "eagle-import") (part "R-US_0207/15"))
    )
    (comp (ref "R20")
      (value "390")
      (footprint "eagle-import:0207_10")
      (libsource (lib "eagle-import") (part "R-US_0207/10"))
    )
    (comp (ref "R21")
      (value "180")
      (footprint "eagle-import:0207_10")
      (libsource (lib "eagle-import") (part "R-US_0207/10"))
    )
  )
  (nets
    (net (code "1") (name "+3V") (class "Default")
      (node (ref "C45") (pin "1") (pinfunction "1_1") (pintype "passive"))
      (node (ref "E1") (pin "10") (pinfunction "ENT_10") (pintype "input"))
      (node (ref "E1") (pin "7") (pinfunction "ENP_7") (pintype "input"))
      (node (ref "E1") (pin "9") (pinfunction "LD_9") (pintype "input"))
      (node (ref "E15") (pin "13") (pinfunction "CLR_13") (pintype "input"))
      (node (ref "E18") (pin "10") (pinfunction "PRE_10") (pintype "input"))
      (node (ref "E19") (pin "1") (pinfunction "CLR_1") (pintype "input"))
      (node (ref "E19") (pin "10") (pinfunction "PRE_10") (pintype "input"))
      (node (ref "E2") (pin "10") (pinfunction "ENT_10") (pintype "input"))
      (node (ref "E2") (pin "7") (pinfunction "ENP_7") (pintype "input"))
      (node (ref "E20") (pin "4") (pinfunction "PRE_4") (pintype "input"))
      (node (ref "E21") (pin "10") (pinfunction "PRE_10") (pintype "input"))
      (node (ref "E24") (pin "10") (pinfunction "PRE_10") (pintype "input"))
      (node (ref "E3") (pin "9") (pinfunction "LD_9") (pintype "input"))
      (node (ref "E37") (pin "13") (pinfunction "CLR_13") (pintype "input"))
      (node (ref "E37") (pin "4") (pinfunction "PRE_4") (pintype "input"))
      (node (ref "E38") (pin "11") (pinfunction "CLR_11") (pintype "input"))
      (node (ref "E38") (pin "3") (pinfunction "CLR_3") (pintype "input"))
      (node (ref "E4") (pin "9") (pinfunction "LD_9") (pintype "input"))
      (node (ref "E41") (pin "10") (pinfunction "PRE_10") (pintype "input"))
      (node (ref "E41") (pin "4") (pinfunction "PRE_4") (pintype "input"))
      (node (ref "E43") (pin "11") (pinfunction "CLR_11") (pintype "input"))
      (node (ref "E43") (pin "3") (pinfunction "CLR_3") (pintype "input"))
      (node (ref "E5") (pin "10") (pinfunction "ENT_10") (pintype "input"))
      (node (ref "R43") (pin "1") (pinfunction "1_1") (pintype "passive"))
      (node (ref "R44") (pin "2") (pinfunction "2_2") (pintype "passive"))
    )
    (net (code "2") (name "6RK3_OK") (class "Default")
      (node (ref "E32") (pin "12") (pinfunction "I0_12") (pintype "input"))
      (node (ref "E50") (pin "6") (pinfunction "I0_6") (pintype "input"))
      (node (ref "E9") (pin "9") (pinfunction "I_9") (pintype "input"))
      (node (ref "F") (pin "A2") (pinfunction "P_A2") (pintype "passive"))
    )
    (net (code "3") (name "12TH_BIT_OK") (class "Default")
      (node (ref "E13") (pin "13") (pinfunction "O_13") (pintype "output"))
      (node (ref "F") (pin "A1") (pinfunction "P_A1") (pintype "passive"))
    )
    (net (code "4") (name "12TH_CARRY") (class "Default")
      (node (ref "E11") (pin "6") (pinfunction "O_6") (pintype "output"))
      (node (ref "E12") (pin "10") (pinfunction "I1_10") (pintype "input"))
      (node (ref "E12") (pin "5") (pinfunction "I1_5") (pintype "input"))
      (node (ref "E3") (pin "10") (pinfunction "ENT_10") (pintype "input"))
      (node (ref "E3") (pin "7") (pinfunction "ENP_7") (pintype "input"))
    )
    (net (code "5") (name "16TH_BIT") (class "Default")
      (node (ref "E11") (pin "10") (pinfunction "O_10") (pintype "output"))
      (node (ref "E27") (pin "5") (pinfunction "I1_5") (pintype "input"))
    )
    (net (code "6") (name "16_CARRY") (class "Default")
      (node (ref "E1") (pin "15") (pinfunction "RCO_15") (pintype "output"))
      (node (ref "E12") (pin "13") (pinfunction "I1_13") (pintype "input"))
      (node (ref "TP1") (pin "P$1") (pinfunction "P_P$1") (pintype "passive"))
    )
    (net (code "7") (name "128TH_WORD") (class "Default")
      (node (ref "E14") (pin "5") (pinfunction "I1_5") (pintype "input"))
      (node (ref "E4") (pin "11") (pinfunction "QD_11") (pintype "output"))
    )
    (net (code "8") (name "ACKNOWLEDGE") (class "Default")
      (node (ref "E26") (pin "9") (pinfunction "I1_9") (pintype "input"))
      (node (ref "E42") (pin "2") (pinfunction "O_2") (pintype "output"))
    )
    (net (code "9") (name "BDATA7") (class "Default")
      (node (ref "E") (pin "R2") (pinfunction "P_R2") (pintype "passive"))
      (node (ref "E46") (pin "2") (pinfunction "A_2") (pintype "input"))
    )
    (net (code "10") (name "BDATA8") (class "Default")
      (node (ref "E") (pin "M1") (pinfunction "P_M1") (pintype "passive"))
      (node (ref "E46") (pin "3") (pinfunction "B_3") (pintype "input"))
      (node (ref "E52") (pin "2") (pinfunction "O_2") (pintype "output"))
    )
    (net (code "11") (name "BDATA9") (class "Default")
      (node (ref "E") (pin "L1") (pinfunction "P_L1") (pintype "passive"))
      (node (ref "E46") (pin "4") (pinfunction "C_4") (pintype "input"))
      (node (ref "E52") (pin "3") (pinfunction "O_3") (pintype "output"))
    )
    (net (code "12") (name "BDATA10") (class "Default")
      (node (ref "E") (pin "K1") (pinfunction "P_K1") (pintype "passive"))
      (node (ref "E46") (pin "6") (pinfunction "D_6") (pintype "input"))
      (node (ref "E52") (pin "14") (pinfunction "O_14") (pintype "output"))
    )
    (net (code "13") (name "BDATA11") (class "Default")
      (node (ref "E") (pin "J1") (pinfunction "P_J1") (pintype "passive"))
      (node (ref "E46") (pin "7") (pinfunction "E_7") (pintype "input"))
      (node (ref "E52") (pin "13") (pinfunction "O_13") (pintype "output"))
    )
    (net (code "14") (name "BRK_ENAB_CLK") (class "Default")
      (node (ref "E8") (pin "6") (pinfunction "O_6") (pintype "output"))
      (node (ref "F") (pin "K2") (pinfunction "P_K2") (pintype "passive"))
    )
    (net (code "15") (name "BRK_IN_CLK") (class "Default")
      (node (ref "E7") (pin "4") (pinfunction "O_4") (pintype "output"))
      (node (ref "F") (pin "U2") (pinfunction "P_U2") (pintype "passive"))
    )
    (net (code "16") (name "BTP2") (class "Default")
      (node (ref "E13") (pin "6") (pinfunction "I1_6") (pintype "input"))
      (node (ref "F") (pin "H2") (pinfunction "P_H2") (pintype "passive"))
    )
    (net (code "17") (name "BTP3") (class "Default")
      (node (ref "E32") (pin "4") (pinfunction "I0_4") (pintype "input"))
      (node (ref "F") (pin "J1") (pinfunction "P_J1") (pintype "passive"))
    )
    (net (code "18") (name "BTP3_OK") (class "Default")
      (node (ref "E13") (pin "8") (pinfunction "I0_8") (pintype "input"))
      (node (ref "F") (pin "M2") (pinfunction "P_M2") (pintype "passive"))
    )
    (net (code "19") (name "B_IDLE") (class "Default")
      (node (ref "E35") (pin "10") (pinfunction "O_10") (pintype "output"))
      (node (ref "E53") (pin "12") (pinfunction "I1_12") (pintype "input"))
      (node (ref "E54") (pin "11") (pinfunction "I0_11") (pintype "input"))
      (node (ref "R26") (pin "1") (pinfunction "1_1") (pintype "passive"))
    )
    (net (code "20") (name "B_LAST_BRK") (class "Default")
      (node (ref "E5") (pin "15") (pinfunction "RCO_15") (pintype "output"))
      (node (ref "F") (pin "L2") (pinfunction "P_L2") (pintype "passive"))
    )
    (net (code "21") (name "B_WRT_CLK") (class "Default")
      (node (ref "E27") (pin "9") (pinfunction "I0_9") (pintype "input"))
      (node (ref "E29") (pin "13") (pinfunction "O_13") (pintype "output"))
      (node (ref "E35") (pin "13") (pinfunction "I_13") (pintype "input"))
    )
    (net (code "22") (name "CLR_CNTRS") (class "Default")
      (node (ref "E10") (pin "6") (pinfunction "O_6") (pintype "output"))
      (node (ref "E11") (pin "3") (pinfunction "I_3") (pintype "input"))
    )
    (net (code "23") (name "CLR_DRIVE_CMD") (class "Default")
      (node (ref "E18") (pin "11") (pinfunction "CLK_11") (pintype "input"))
      (node (ref "E9") (pin "10") (pinfunction "O_10") (pintype "output"))
    )
    (net (code "24") (name "CLR_STATES") (class "Default")
      (node (ref "E23") (pin "12") (pinfunction "I1_12") (pintype "input"))
      (node (ref "E23") (pin "2") (pinfunction "I0_2") (pintype "input"))
      (node (ref "E23") (pin "8") (pinfunction "I0_8") (pintype "input"))
      (node (ref "E26") (pin "5") (pinfunction "I0_5") (pintype "input"))
      (node (ref "E26") (pin "8") (pinfunction "I0_8") (pintype "input"))
      (node (ref "E29") (pin "5") (pinfunction "I0_5") (pintype "input"))
      (node (ref "E9") (pin "6") (pinfunction "O_6") (pintype "output"))
    )
    (net (code "25") (name "CRC16") (class "Default")
      (node (ref "E") (pin "N2") (pinfunction "P_N2") (pintype "passive"))
      (node (ref "E33") (pin "1") (pinfunction "I0_1") (pintype "input"))
    )
    (net (code "26") (name "CRC_DATA") (class "Default")
      (node (ref "E") (pin "A1") (pinfunction "P_A1") (pintype "passive"))
      (node (ref "E28") (pin "8") (pinfunction "O8_8") (pintype "output"))
    )
    (net (code "27") (name "CRC_STATE") (class "Default")
      (node (ref "E21") (pin "12") (pinfunction "D_12") (pintype "input"))
      (node (ref "E21") (pin "5") (pinfunction "Q_5") (pintype "output"))
      (node (ref "E23") (pin "9") (pinfunction "I1_9") (pintype "input"))
      (node (ref "E28") (pin "12") (pinfunction "I12_12") (pintype "input"))
    )
    (net (code "28") (name "DATA_CLK") (class "Default")
      (node (ref "E16") (pin "8") (pinfunction "O_8") (pintype "output"))
      (node (ref "E17") (pin "1") (pinfunction "I0_1") (pintype "input"))
    )
    (net (code "29") (name "DATA_CLK_OK") (class "Default")
      (node (ref "E17") (pin "8") (pinfunction "O_8") (pintype "output"))
      (node (ref "F") (pin "M1") (pinfunction "P_M1") (pintype "passive"))
    )
    (net (code "30") (name "DATA_ENABLE") (class "Default")
      (node (ref "E") (pin "U1") (pinfunction "P_U1") (pintype "passive"))
      (node (ref "E6") (pin "10") (pinfunction "ENT_10") (pintype "input"))
      (node (ref "E6") (pin "7") (pinfunction "ENP_7") (pintype "input"))
    )
    (net (code "31") (name "DATA_IN") (class "Default")
      (node (ref "E15") (pin "5") (pinfunction "Q_5") (pintype "output"))
      (node (ref "E28") (pin "1") (pinfunction "I1_1") (pintype "input"))
      (node (ref "E28") (pin "11") (pinfunction "I11_11") (pintype "input"))
      (node (ref "E28") (pin "13") (pinfunction "I13_13") (pintype "input"))
      (node (ref "E8") (pin "9") (pinfunction "I0_9") (pintype "input"))
    )
    (net (code "32") (name "DATA_STATE") (class "Default")
      (node (ref "E14") (pin "10") (pinfunction "I1_10") (pintype "input"))
      (node (ref "E17") (pin "2") (pinfunction "I1_2") (pintype "input"))
      (node (ref "E21") (pin "2") (pinfunction "D_2") (pintype "input"))
      (node (ref "E22") (pin "5") (pinfunction "Q_5") (pintype "output"))
      (node (ref "E23") (pin "11") (pinfunction "I0_11") (pintype "input"))
      (node (ref "E23") (pin "5") (pinfunction "I0_5") (pintype "input"))
      (node (ref "E28") (pin "2") (pinfunction "I2_2") (pintype "input"))
      (node (ref "E28") (pin "3") (pinfunction "I3_3") (pintype "input"))
      (node (ref "E33") (pin "10") (pinfunction "I1_10") (pintype "input"))
      (node (ref "E40") (pin "9") (pinfunction "I1_9") (pintype "input"))
      (node (ref "E43") (pin "10") (pinfunction "B_10") (pintype "input"))
      (node (ref "E8") (pin "2") (pinfunction "I1_2") (pintype "input"))
    )
    (net (code "33") (name "DISK_OK") (class "Default")
      (node (ref "E16") (pin "3") (pinfunction "O_3") (pintype "output"))
      (node (ref "E19") (pin "3") (pinfunction "CLK_3") (pintype "input"))
      (node (ref "E24") (pin "3") (pinfunction "CLK_3") (pintype "input"))
    )
    (net (code "34") (name "DRV_REVO") (class "Default")
      (node (ref "E53") (pin "13") (pinfunction "O_13") (pintype "output"))
      (node (ref "F") (pin "C2") (pinfunction "P_C2") (pintype "passive"))
    )
    (net (code "35") (name "DSK_SEC2") (class "Default")
      (node (ref "E42") (pin "3") (pinfunction "O_3") (pintype "output"))
      (node (ref "E47") (pin "12") (pinfunction "A1_12") (pintype "input"))
    )
    (net (code "36") (name "END_STATE") (class "Default")
      (node (ref "E21") (pin "9") (pinfunction "Q_9") (pintype "output"))
      (node (ref "E23") (pin "3") (pinfunction "I1_3") (pintype "input"))
      (node (ref "E30") (pin "3") (pinfunction "I1_3") (pintype "input"))
      (node (ref "E39") (pin "5") (pinfunction "I2_5") (pintype "input"))
      (node (ref "E43") (pin "2") (pinfunction "B_2") (pintype "input"))
    )
    (net (code "37") (name "FILE_RDY") (class "Default")
      (node (ref "E") (pin "E1") (pinfunction "P_E1") (pintype "passive"))
      (node (ref "E18") (pin "12") (pinfunction "D_12") (pintype "input"))
      (node (ref "E19") (pin "12") (pinfunction "D_12") (pintype "input"))
      (node (ref "E54") (pin "2") (pinfunction "O_2") (pintype "output"))
    )
    (net (code "38") (name "FUNCTION00") (class "Default")
      (node (ref "E") (pin "U2") (pinfunction "P_U2") (pintype "passive"))
      (node (ref "E31") (pin "1") (pinfunction "1C_1") (pintype "input"))
      (node (ref "E31") (pin "15") (pinfunction "2C_15") (pintype "input"))
    )
    (net (code "39") (name "FUNCTION01") (class "Default")
      (node (ref "E") (pin "V2") (pinfunction "P_V2") (pintype "passive"))
      (node (ref "E31") (pin "3") (pinfunction "B_3") (pintype "input"))
    )
    (net (code "40") (name "FUNCTION02") (class "Default")
      (node (ref "E") (pin "T2") (pinfunction "P_T2") (pintype "passive"))
      (node (ref "E31") (pin "13") (pinfunction "A_13") (pintype "input"))
    )
    (net (code "41") (name "GND") (class "Default")
      (node (ref "C1") (pin "2") (pinfunction "2_2") (pintype "passive"))
      (node (ref "C10") (pin "2") (pinfunction "2_2") (pintype "passive"))
      (node (ref "C11") (pin "2") (pinfunction "2_2") (pintype "passive"))
      (node (ref "C12") (pin "2") (pinfunction "2_2") (pintype "passive"))
      (node (ref "C13") (pin "2") (pinfunction "2_2") (pintype "passive"))
      (node (ref "C14") (pin "2") (pinfunction "2_2") (pintype "passive"))
      (node (ref "C15") (pin "2") (pinfunction "2_2") (pintype "passive"))
      (node (ref "C16") (pin "2") (pinfunction "2_2") (pintype "passive"))
      (node (ref "C17") (pin "2") (pinfunction "2_2") (pintype "passive"))
      (node (ref "C18") (pin "2") (pinfunction "2_2") (pintype "passive"))
      (node (ref "C19") (pin "2") (pinfunction "2_2") (pintype "passive"))
      (node (ref "C2") (pin "2") (pinfunction "2_2") (pintype "passive"))
      (node (ref "C20") (pin "2") (pinfunction "2_2") (pintype "passive"))
      (node (ref "C21") (pin "2") (pinfunction "2_2") (pintype "passive"))
      (node (ref "C22") (pin "2") (pinfunction "2_2") (pintype "passive"))
      (node (ref "C23") (pin "2") (pinfunction "2_2") (pintype "passive"))
      (node (ref "C24") (pin "2") (pinfunction "2_2") (pintype "passive"))
      (node (ref "C25") (pin "2") (pinfunction "2_2") (pintype "passive"))
      (node (ref "C27") (pin "-") (pinfunction "-_-") (pintype "passive"))
      (node (ref "C28") (pin "-") (pinfunction "-_-") (pintype "passive"))
      (node (ref "C29") (pin "-") (pinfunction "-_-") (pintype "passive"))
      (node (ref "C3") (pin "2") (pinfunction "2_2") (pintype "passive"))
      (node (ref "C30") (pin "2") (pinfunction "2_2") (pintype "passive"))
      (node (ref "C32") (pin "2") (pinfunction "2_2") (pintype "passive"))
      (node (ref "C34") (pin "2") (pinfunction "2_2") (pintype "passive"))
      (node (ref "C35") (pin "2") (pinfunction "2_2") (pintype "passive"))
      (node (ref "C39") (pin "2") (pinfunction "2_2") (pintype "passive"))
      (node (ref "C4") (pin "2") (pinfunction "2_2") (pintype "passive"))
      (node (ref "C40") (pin "2") (pinfunction "2_2") (pintype "passive"))
      (node (ref "C41") (pin "2") (pinfunction "2_2") (pintype "passive"))
      (node (ref "C42") (pin "2") (pinfunction "2_2") (pintype "passive"))
      (node (ref "C43") (pin "2") (pinfunction "2_2") (pintype "passive"))
      (node (ref "C44") (pin "2") (pinfunction "2_2") (pintype "passive"))
      (node (ref "C45") (pin "2") (pinfunction "2_2") (pintype "passive"))
      (node (ref "C5") (pin "2") (pinfunction "2_2") (pintype "passive"))
      (node (ref "C6") (pin "2") (pinfunction "2_2") (pintype "passive"))
      (node (ref "C7") (pin "2") (pinfunction "2_2") (pintype "passive"))
      (node (ref "C8") (pin "2") (pinfunction "2_2") (pintype "passive"))
      (node (ref "C9") (pin "2") (pinfunction "2_2") (pintype "passive"))
      (node (ref "E1") (pin "3") (pinfunction "A_3") (pintype "input"))
      (node (ref "E1") (pin "4") (pinfunction "B_4") (pintype "input"))
      (node (ref "E1") (pin "5") (pinfunction "C_5") (pintype "input"))
      (node (ref "E1") (pin "6") (pinfunction "D_6") (pintype "input"))
      (node (ref "E15") (pin "2") (pinfunction "D_2") (pintype "input"))
      (node (ref "E18") (pin "2") (pinfunction "D_2") (pintype "input"))
      (node (ref "E2") (pin "3") (pinfunction "A_3") (pintype "input"))
      (node (ref "E2") (pin "4") (pinfunction "B_4") (pintype "input"))
      (node (ref "E2") (pin "5") (pinfunction "C_5") (pintype "input"))
      (node (ref "E2") (pin "6") (pinfunction "D_6") (pintype "input"))
      (node (ref "E3") (pin "3") (pinfunction "A_3") (pintype "input"))
      (node (ref "E3") (pin "4") (pinfunction "B_4") (pintype "input"))
      (node (ref "E3") (pin "5") (pinfunction "C_5") (pintype "input"))
      (node (ref "E3") (pin "6") (pinfunction "D_6") (pintype "input"))
      (node (ref "E31") (pin "14") (pinfunction "2G_14") (pintype "input"))
      (node (ref "E31") (pin "2") (pinfunction "1G_2") (pintype "input"))
      (node (ref "E38") (pin "1") (pinfunction "A_1") (pintype "input"))
      (node (ref "E4") (pin "3") (pinfunction "A_3") (pintype "input"))
      (node (ref "E4") (pin "4") (pinfunction "B_4") (pintype "input"))
      (node (ref "E4") (pin "5") (pinfunction "C_5") (pintype "input"))
      (node (ref "E4") (pin "6") (pinfunction "D_6") (pintype "input"))
      (node (ref "E42") (pin "5") (pinfunction "I1_5") (pintype "input"))
      (node (ref "E42") (pin "6") (pinfunction "I0_6") (pintype "input"))
      (node (ref "E43") (pin "9") (pinfunction "A_9") (pintype "input"))
      (node (ref "E46") (pin "9") (pinfunction "SER_9") (pintype "input"))
      (node (ref "E47") (pin "2") (pinfunction "A<B_I_2") (pintype "input"))
      (node (ref "E47") (pin "4") (pinfunction "A>B_I_4") (pintype "input"))
      (node (ref "E5") (pin "3") (pinfunction "A_3") (pintype "input"))
      (node (ref "E5") (pin "4") (pinfunction "B_4") (pintype "input"))
      (node (ref "E5") (pin "5") (pinfunction "C_5") (pintype "input"))
      (node (ref "E53") (pin "10") (pinfunction "I1_10") (pintype "input"))
      (node (ref "E53") (pin "5") (pinfunction "I1_5") (pintype "input"))
      (node (ref "E53") (pin "7") (pinfunction "I1_7") (pintype "input"))
      (node (ref "E6") (pin "3") (pinfunction "A_3") (pintype "input"))
      (node (ref "E6") (pin "4") (pinfunction "B_4") (pintype "input"))
      (node (ref "E6") (pin "5") (pinfunction "C_5") (pintype "input"))
      (node (ref "E6") (pin "6") (pinfunction "D_6") (pintype "input"))
      (node (ref "J1") (pin "A") (pinfunction "P_A") (pintype "passive"))
      (node (ref "J1") (pin "AA") (pinfunction "P_AA") (pintype "passive"))
      (node (ref "J1") (pin "B") (pinfunction "P_B") (pintype "passive"))
      (node (ref "J1") (pin "C") (pinfunction "P_C") (pintype "passive"))
      (node (ref "J1") (pin "CC") (pinfunction "P_CC") (pintype "passive"))
      (node (ref "J1") (pin "E") (pinfunction "P_E") (pintype "passive"))
      (node (ref "J1") (pin "EE") (pinfunction "P_EE") (pintype "passive"))
      (node (ref "J1") (pin "H") (pinfunction "P_H") (pintype "passive"))
      (node (ref "J1") (pin "HH") (pinfunction "P_HH") (pintype "passive"))
      (node (ref "J1") (pin "K") (pinfunction "P_K") (pintype "passive"))
      (node (ref "J1") (pin "KK") (pinfunction "P_KK") (pintype "passive"))
      (node (ref "J1") (pin "M") (pinfunction "P_M") (pintype "passive"))
      (node (ref "J1") (pin "MM") (pinfunction "P_MM") (pintype "passive"))
      (node (ref "J1") (pin "P") (pinfunction "P_P") (pintype "passive"))
      (node (ref "J1") (pin "PP") (pinfunction "P_PP") (pintype "passive"))
      (node (ref "J1") (pin "S") (pinfunction "P_S") (pintype "passive"))
      (node (ref "J1") (pin "SS") (pinfunction "P_SS") (pintype "passive"))
      (node (ref "J1") (pin "U") (pinfunction "P_U") (pintype "passive"))
      (node (ref "J1") (pin "UU") (pinfunction "P_UU") (pintype "passive"))
      (node (ref "J1") (pin "W") (pinfunction "P_W") (pintype "passive"))
      (node (ref "J1") (pin "Y") (pinfunction "P_Y") (pintype "passive"))
      (node (ref "J2") (pin "B") (pinfunction "P_B") (pintype "passive"))
      (node (ref "J2") (pin "BB") (pinfunction "P_BB") (pintype "passive"))
      (node (ref "J2") (pin "D") (pinfunction "P_D") (pintype "passive"))
      (node (ref "J2") (pin "DD") (pinfunction "P_DD") (pintype "passive"))
      (node (ref "J2") (pin "F") (pinfunction "P_F") (pintype "passive"))
      (node (ref "J2") (pin "FF") (pinfunction "P_FF") (pintype "passive"))
      (node (ref "J2") (pin "J") (pinfunction "P_J") (pintype "passive"))
      (node (ref "J2") (pin "JJ") (pinfunction "P_JJ") (pintype "passive"))
      (node (ref "J2") (pin "L") (pinfunction "P_L") (pintype "passive"))
      (node (ref "J2") (pin "LL") (pinfunction "P_LL") (pintype "passive"))
      (node (ref "J2") (pin "N") (pinfunction "P_N") (pintype "passive"))
      (node (ref "J2") (pin "NN") (pinfunction "P_NN") (pintype "passive"))
      (node (ref "J2") (pin "R") (pinfunction "P_R") (pintype "passive"))
      (node (ref "J2") (pin "RR") (pinfunction "P_RR") (pintype "passive"))
      (node (ref "J2") (pin "T") (pinfunction "P_T") (pintype "passive"))
      (node (ref "J2") (pin "TT") (pinfunction "P_TT") (pintype "passive"))
      (node (ref "J2") (pin "V") (pinfunction "P_V") (pintype "passive"))
      (node (ref "J2") (pin "VV") (pinfunction "P_VV") (pintype "passive"))
      (node (ref "J2") (pin "X") (pinfunction "P_X") (pintype "passive"))
      (node (ref "J2") (pin "Z") (pinfunction "P_Z") (pintype "passive"))
      (node (ref "OMNIBUS") (pin "AC2") (pinfunction "1_AC2") (pintype "bidirectional"))
      (node (ref "OMNIBUS") (pin "AF1") (pinfunction "1_AF1") (pintype "bidirectional"))
      (node (ref "OMNIBUS") (pin "AF2") (pinfunction "1_AF2") (pintype "bidirectional"))
      (node (ref "OMNIBUS") (pin "AN1") (pinfunction "1_AN1") (pintype "bidirectional"))
      (node (ref "OMNIBUS") (pin "AN2") (pinfunction "1_AN2") (pintype "bidirectional"))
      (node (ref "OMNIBUS") (pin "AT1") (pinfunction "1_AT1") (pintype "bidirectional"))
      (node (ref "OMNIBUS") (pin "AT2") (pinfunction "1_AT2") (pintype "bidirectional"))
      (node (ref "OMNIBUS") (pin "BC1") (pinfunction "1_BC1") (pintype "bidirectional"))
      (node (ref "OMNIBUS") (pin "BC2") (pinfunction "1_BC2") (pintype "bidirectional"))
      (node (ref "OMNIBUS") (pin "BF1") (pinfunction "1_BF1") (pintype "bidirectional"))
      (node (ref "OMNIBUS") (pin "BF2") (pinfunction "1_BF2") (pintype "bidirectional"))
      (node (ref "OMNIBUS") (pin "BN1") (pinfunction "1_BN1") (pintype "bidirectional"))
      (node (ref "OMNIBUS") (pin "BN2") (pinfunction "1_BN2") (pintype "bidirectional"))
      (node (ref "OMNIBUS") (pin "BT1") (pinfunction "1_BT1") (pintype "bidirectional"))
      (node (ref "OMNIBUS") (pin "BT2") (pinfunction "1_BT2") (pintype "bidirectional"))
      (node (ref "OMNIBUS") (pin "CC1") (pinfunction "1_CC1") (pintype "bidirectional"))
      (node (ref "OMNIBUS") (pin "CC2") (pinfunction "1_CC2") (pintype "bidirectional"))
      (node (ref "OMNIBUS") (pin "CF1") (pinfunction "1_CF1") (pintype "bidirectional"))
      (node (ref "OMNIBUS") (pin "CF2") (pinfunction "1_CF2") (pintype "bidirectional"))
      (node (ref "OMNIBUS") (pin "CN1") (pinfunction "1_CN1") (pintype "bidirectional"))
      (node (ref "OMNIBUS") (pin "CN2") (pinfunction "1_CN2") (pintype "bidirectional"))
      (node (ref "OMNIBUS") (pin "CT1") (pinfunction "1_CT1") (pintype "bidirectional"))
      (node (ref "OMNIBUS") (pin "CT2") (pinfunction "1_CT2") (pintype "bidirectional"))
      (node (ref "OMNIBUS") (pin "DC1") (pinfunction "1_DC1") (pintype "bidirectional"))
      (node (ref "OMNIBUS") (pin "DC2") (pinfunction "1_DC2") (pintype "bidirectional"))
      (node (ref "OMNIBUS") (pin "DF1") (pinfunction "1_DF1") (pintype "bidirectional"))
      (node (ref "OMNIBUS") (pin "DF2") (pinfunction "1_DF2") (pintype "bidirectional"))
      (node (ref "OMNIBUS") (pin "DN1") (pinfunction "1_DN1") (pintype "bidirectional"))
      (node (ref "OMNIBUS") (pin "DN2") (pinfunction "1_DN2") (pintype "bidirectional"))
      (node (ref "OMNIBUS") (pin "DT1") (pinfunction "1_DT1") (pintype "bidirectional"))
      (node (ref "OMNIBUS") (pin "DT2") (pinfunction "1_DT2") (pintype "bidirectional"))
      (node (ref "R11") (pin "1") (pinfunction "1_1") (pintype "passive"))
      (node (ref "R16") (pin "1") (pinfunction "1_1") (pintype "passive"))
      (node (ref "R20") (pin "1") (pinfunction "1_1") (pintype "passive"))
      (node (ref "R23") (pin "1") (pinfunction "1_1") (pintype "passive"))
      (node (ref "R25") (pin "1") (pinfunction "1_1") (pintype "passive"))
      (node (ref "R27") (pin "1") (pinfunction "1_1") (pintype "passive"))
      (node (ref "R30") (pin "1") (pinfunction "1_1") (pintype "passive"))
      (node (ref "R31") (pin "1") (pinfunction "1_1") (pintype "passive"))
      (node (ref "R34") (pin "1") (pinfunction "1_1") (pintype "passive"))
      (node (ref "R35") (pin "1") (pinfunction "1_1") (pintype "passive"))
      (node (ref "R37") (pin "1") (pinfunction "1_1") (pintype "passive"))
      (node (ref "R39") (pin "1") (pinfunction "1_1") (pintype "passive"))
      (node (ref "R41") (pin "1") (pinfunction "1_1") (pintype "passive"))
      (node (ref "R44") (pin "1") (pinfunction "1_1") (pintype "passive"))
      (node (ref "R45") (pin "1") (pinfunction "1_1") (pintype "passive"))
      (node (ref "R47") (pin "1") (pinfunction "1_1") (pintype "passive"))
      (node (ref "R49") (pin "1") (pinfunction "1_1") (pintype "passive"))
      (node (ref "R51") (pin "1") (pinfunction "1_1") (pintype "passive"))
      (node (ref "R53") (pin "1") (pinfunction "1_1") (pintype "passive"))
    )
    (net (code "42") (name "GO") (class "Default")
      (node (ref "E19") (pin "11") (pinfunction "CLK_11") (pintype "input"))
      (node (ref "E45") (pin "11") (pinfunction "O_11") (pintype "output"))
      (node (ref "E9") (pin "1") (pinfunction "I_1") (pintype "input"))
    )
    (net (code "43") (name "HALF_BLOCK") (class "Default")
      (node (ref "E") (pin "S2") (pinfunction "P_S2") (pintype "passive"))
      (node (ref "E14") (pin "4") (pinfunction "I0_4") (pintype "input"))
      (node (ref "E5") (pin "6") (pinfunction "D_6") (pintype "input"))
    )
    (net (code "44") (name "HEADER_A") (class "Default")
      (node (ref "E19") (pin "6") (pinfunction "~{Q}_6") (pintype "output"))
      (node (ref "E20") (pin "2") (pinfunction "D_2") (pintype "input"))
    )
    (net (code "45") (name "HEADER_B") (class "Default")
      (node (ref "E20") (pin "12") (pinfunction "D_12") (pintype "input"))
      (node (ref "E20") (pin "5") (pinfunction "Q_5") (pintype "output"))
      (node (ref "E26") (pin "3") (pinfunction "I1_3") (pintype "input"))
      (node (ref "E30") (pin "6") (pinfunction "I1_6") (pintype "input"))
    )
    (net (code "46") (name "HEADER_C") (class "Default")
      (node (ref "E20") (pin "9") (pinfunction "Q_9") (pintype "output"))
      (node (ref "E26") (pin "6") (pinfunction "I1_6") (pintype "input"))
      (node (ref "E27") (pin "4") (pinfunction "I0_4") (pintype "input"))
      (node (ref "E28") (pin "10") (pinfunction "I10_10") (pintype "input"))
    )
    (net (code "47") (name "HEADER_D") (class "Default")
      (node (ref "E22") (pin "12") (pinfunction "D_12") (pintype "input"))
      (node (ref "E24") (pin "9") (pinfunction "Q_9") (pintype "output"))
      (node (ref "E29") (pin "3") (pinfunction "I1_3") (pintype "input"))
      (node (ref "E37") (pin "1") (pinfunction "CLR_1") (pintype "input"))
      (node (ref "E41") (pin "11") (pinfunction "CLK_11") (pintype "input"))
    )
    (net (code "48") (name "HEADER_E") (class "Default")
      (node (ref "E13") (pin "2") (pinfunction "I0_2") (pintype "input"))
      (node (ref "E22") (pin "2") (pinfunction "D_2") (pintype "input"))
      (node (ref "E22") (pin "9") (pinfunction "Q_9") (pintype "output"))
      (node (ref "E29") (pin "6") (pinfunction "I1_6") (pintype "input"))
    )
    (net (code "49") (name "IDLE") (class "Default")
      (node (ref "E") (pin "C1") (pinfunction "P_C1") (pintype "passive"))
      (node (ref "E18") (pin "6") (pinfunction "~{Q}_6") (pintype "output"))
      (node (ref "E26") (pin "2") (pinfunction "I0_2") (pintype "input"))
      (node (ref "E29") (pin "2") (pinfunction "I0_2") (pintype "input"))
      (node (ref "E29") (pin "8") (pinfunction "I0_8") (pintype "input"))
    )
    (net (code "50") (name "INC_CNTRS") (class "Default")
      (node (ref "E10") (pin "12") (pinfunction "O_12") (pintype "output"))
      (node (ref "E11") (pin "1") (pinfunction "I_1") (pintype "input"))
      (node (ref "E12") (pin "12") (pinfunction "I0_12") (pintype "input"))
      (node (ref "E12") (pin "4") (pinfunction "I0_4") (pintype "input"))
    )
    (net (code "51") (name "INH_12TH_BIT") (class "Default")
      (node (ref "E13") (pin "12") (pinfunction "I1_12") (pintype "input"))
      (node (ref "E15") (pin "8") (pinfunction "~{Q}_8") (pintype "output"))
    )
    (net (code "52") (name "INITIALIZE") (class "Default")
      (node (ref "OMNIBUS") (pin "CR1") (pinfunction "1_CR1") (pintype "bidirectional"))
      (node (ref "SV8") (pin "1") (pinfunction "1_1") (pintype "passive"))
    )
    (net (code "53") (name "LAST_BRK") (class "Default")
      (node (ref "E39") (pin "4") (pinfunction "I1_4") (pintype "input"))
      (node (ref "F") (pin "N2") (pinfunction "P_N2") (pintype "passive"))
    )
    (net (code "54") (name "LAST_WORD") (class "Default")
      (node (ref "C40") (pin "1") (pinfunction "1_1") (pintype "passive"))
      (node (ref "E12") (pin "9") (pinfunction "I0_9") (pintype "input"))
      (node (ref "R55") (pin "2") (pinfunction "2_2") (pintype "passive"))
    )
    (net (code "55") (name "LAST_WORD_PL") (class "Default")
      (node (ref "E11") (pin "8") (pinfunction "O_8") (pintype "output"))
      (node (ref "F") (pin "E1") (pinfunction "P_E1") (pintype "passive"))
    )
    (net (code "56") (name "LD_DISK_ADDRS") (class "Default")
      (node (ref "E") (pin "M2") (pinfunction "P_M2") (pintype "passive"))
      (node (ref "E32") (pin "6") (pinfunction "O_6") (pintype "output"))
      (node (ref "E39") (pin "1") (pinfunction "I0_1") (pintype "input"))
      (node (ref "E46") (pin "8") (pinfunction "PE_8") (pintype "input"))
    )
    (net (code "57") (name "NOT_CHK_HEADER_CMD") (class "Default")
      (node (ref "E24") (pin "2") (pinfunction "D_2") (pintype "input"))
      (node (ref "E34") (pin "8") (pinfunction "O_8") (pintype "output"))
    )
    (net (code "58") (name "Net-(C26-Pad1)") (class "Default")
      (node (ref "C26") (pin "1") (pinfunction "1_1") (pintype "passive"))
      (node (ref "D3") (pin "A") (pinfunction "A_A") (pintype "passive"))
      (node (ref "R19") (pin "1") (pinfunction "1_1") (pintype "passive"))
    )
    (net (code "59") (name "Net-(C33-Pad2)") (class "Default")
      (node (ref "C33") (pin "2") (pinfunction "2_2") (pintype "passive"))
      (node (ref "R5") (pin "1") (pinfunction "1_1") (pintype "passive"))
      (node (ref "W1") (pin "1") (pinfunction "1_1") (pintype "passive"))
    )
    (net (code "60") (name "Net-(C36-Pad2)") (class "Default")
      (node (ref "C36") (pin "2") (pinfunction "2_2") (pintype "passive"))
      (node (ref "R13") (pin "1") (pinfunction "1_1") (pintype "passive"))
      (node (ref "W2") (pin "1") (pinfunction "1_1") (pintype "passive"))
    )
    (net (code "61") (name "Net-(C38-Pad2)") (class "Default")
      (node (ref "C38") (pin "2") (pinfunction "2_2") (pintype "passive"))
      (node (ref "CR1") (pin "2") (pinfunction "2_2") (pintype "passive"))
      (node (ref "R16") (pin "2") (pinfunction "2_2") (pintype "passive"))
    )
    (net (code "62") (name "Net-(CR1-Pad1)") (class "Default")
      (node (ref "CR1") (pin "1") (pinfunction "1_1") (pintype "passive"))
      (node (ref "R14") (pin "1") (pinfunction "1_1") (pintype "passive"))
    )
    (net (code "63") (name "Net-(E3A-RCO)") (class "Default")
      (node (ref "E3") (pin "15") (pinfunction "RCO_15") (pintype "output"))
      (node (ref "E4") (pin "10") (pinfunction "ENT_10") (pintype "input"))
      (node (ref "E4") (pin "7") (pinfunction "ENP_7") (pintype "input"))
    )
    (net (code "64") (name "Net-(E4A-RCO)") (class "Default")
      (node (ref "E4") (pin "15") (pinfunction "RCO_15") (pintype "output"))
      (node (ref "R55") (pin "1") (pinfunction "1_1") (pintype "passive"))
    )
    (net (code "65") (name "Net-(E5A-ENP)") (class "Default")
      (node (ref "E5") (pin "7") (pinfunction "ENP_7") (pintype "input"))
      (node (ref "E6") (pin "15") (pinfunction "RCO_15") (pintype "output"))
    )
    (net (code "66") (name "Net-(E7B-I)") (class "Default")
      (node (ref "E7") (pin "3") (pinfunction "I_3") (pintype "input"))
      (node (ref "E8") (pin "3") (pinfunction "O_3") (pintype "output"))
      (node (ref "E8") (pin "4") (pinfunction "I0_4") (pintype "input"))
    )
    (net (code "67") (name "Net-(E7E-O)") (class "Default")
      (node (ref "E7") (pin "10") (pinfunction "O_10") (pintype "output"))
      (node (ref "R7") (pin "1") (pinfunction "1_1") (pintype "passive"))
    )
    (net (code "68") (name "Net-(E7F-O)") (class "Default")
      (node (ref "E7") (pin "12") (pinfunction "O_12") (pintype "output"))
      (node (ref "R6") (pin "1") (pinfunction "1_1") (pintype "passive"))
    )
    (net (code "69") (name "Net-(E8D-I0)") (class "Default")
      (node (ref "C34") (pin "1") (pinfunction "1_1") (pintype "passive"))
      (node (ref "E8") (pin "12") (pinfunction "I0_12") (pintype "input"))
      (node (ref "R6") (pin "2") (pinfunction "2_2") (pintype "passive"))
    )
    (net (code "70") (name "Net-(E10B-I0)") (class "Default")
      (node (ref "E10") (pin "3") (pinfunction "I0_3") (pintype "input"))
      (node (ref "E12") (pin "3") (pinfunction "O_3") (pintype "output"))
    )
    (net (code "71") (name "Net-(E10C-I0)") (class "Default")
      (node (ref "E10") (pin "9") (pinfunction "I0_9") (pintype "input"))
      (node (ref "E2") (pin "14") (pinfunction "QA_14") (pintype "output"))
    )
    (net (code "72") (name "Net-(E10C-I1)") (class "Default")
      (node (ref "E10") (pin "10") (pinfunction "I1_10") (pintype "input"))
      (node (ref "E2") (pin "13") (pinfunction "QB_13") (pintype "output"))
    )
    (net (code "73") (name "Net-(E10C-I2)") (class "Default")
      (node (ref "E10") (pin "11") (pinfunction "I2_11") (pintype "input"))
      (node (ref "E2") (pin "11") (pinfunction "QD_11") (pintype "output"))
    )
    (net (code "74") (name "Net-(E11F-I)") (class "Default")
      (node (ref "E11") (pin "13") (pinfunction "I_13") (pintype "input"))
      (node (ref "E12") (pin "1") (pinfunction "I0_1") (pintype "input"))
      (node (ref "E9") (pin "12") (pinfunction "O_12") (pintype "output"))
    )
    (net (code "75") (name "Net-(E11F-O)") (class "Default")
      (node (ref "E11") (pin "12") (pinfunction "O_12") (pintype "output"))
      (node (ref "R3") (pin "1") (pinfunction "1_1") (pintype "passive"))
    )
    (net (code "76") (name "Net-(E12A-I1)") (class "Default")
      (node (ref "C32") (pin "1") (pinfunction "1_1") (pintype "passive"))
      (node (ref "E12") (pin "2") (pinfunction "I1_2") (pintype "input"))
      (node (ref "R3") (pin "2") (pinfunction "2_2") (pintype "passive"))
    )
    (net (code "77") (name "Net-(E12B-O)") (class "Default")
      (node (ref "E12") (pin "6") (pinfunction "O_6") (pintype "output"))
      (node (ref "E13") (pin "11") (pinfunction "I0_11") (pintype "input"))
    )
    (net (code "78") (name "Net-(E13A-O)") (class "Default")
      (node (ref "E13") (pin "1") (pinfunction "O_1") (pintype "output"))
      (node (ref "E9") (pin "13") (pinfunction "I_13") (pintype "input"))
    )
    (net (code "79") (name "Net-(E13B-I0)") (class "Default")
      (node (ref "E13") (pin "10") (pinfunction "O_10") (pintype "output"))
      (node (ref "E13") (pin "5") (pinfunction "I0_5") (pintype "input"))
    )
    (net (code "80") (name "Net-(E14B-O)") (class "Default")
      (node (ref "E14") (pin "6") (pinfunction "O_6") (pintype "output"))
      (node (ref "E15") (pin "12") (pinfunction "D_12") (pintype "input"))
    )
    (net (code "81") (name "Net-(E14D-I1)") (class "Default")
      (node (ref "E14") (pin "13") (pinfunction "I1_13") (pintype "input"))
      (node (ref "E40") (pin "4") (pinfunction "O_4") (pintype "output"))
    )
    (net (code "82") (name "Net-(E15B-CLK)") (class "Default")
      (node (ref "C30") (pin "1") (pinfunction "1_1") (pintype "passive"))
      (node (ref "E15") (pin "11") (pinfunction "CLK_11") (pintype "input"))
      (node (ref "R1") (pin "2") (pinfunction "2_2") (pintype "passive"))
    )
    (net (code "83") (name "Net-(E16B-I0)") (class "Default")
      (node (ref "E16") (pin "4") (pinfunction "I0_4") (pintype "input"))
      (node (ref "E30") (pin "1") (pinfunction "O_1") (pintype "output"))
    )
    (net (code "84") (name "Net-(E16B-O)") (class "Default")
      (node (ref "E16") (pin "6") (pinfunction "O_6") (pintype "output"))
      (node (ref "E37") (pin "10") (pinfunction "PRE_10") (pintype "input"))
    )
    (net (code "85") (name "Net-(E16C-I0)") (class "Default")
      (node (ref "E16") (pin "9") (pinfunction "I0_9") (pintype "input"))
      (node (ref "E34") (pin "4") (pinfunction "I1_4") (pintype "input"))
      (node (ref "E36") (pin "1") (pinfunction "I_1") (pintype "input"))
      (node (ref "E39") (pin "10") (pinfunction "I1_10") (pintype "input"))
      (node (ref "E45") (pin "8") (pinfunction "O_8") (pintype "output"))
    )
    (net (code "86") (name "Net-(E16C-I1)") (class "Default")
      (node (ref "E16") (pin "10") (pinfunction "I1_10") (pintype "input"))
      (node (ref "E34") (pin "3") (pinfunction "I0_3") (pintype "input"))
      (node (ref "E41") (pin "5") (pinfunction "Q_5") (pintype "output"))
    )
    (net (code "87") (name "Net-(E16D-I1)") (class "Default")
      (node (ref "C35") (pin "1") (pinfunction "1_1") (pintype "passive"))
      (node (ref "E16") (pin "13") (pinfunction "I1_13") (pintype "input"))
      (node (ref "R7") (pin "2") (pinfunction "2_2") (pintype "passive"))
    )
    (net (code "88") (name "Net-(E17A-O)") (class "Default")
      (node (ref "E17") (pin "3") (pinfunction "O_3") (pintype "output"))
      (node (ref "E17") (pin "4") (pinfunction "I0_4") (pintype "input"))
      (node (ref "E17") (pin "5") (pinfunction "I1_5") (pintype "input"))
    )
    (net (code "89") (name "Net-(E17B-O)") (class "Default")
      (node (ref "E17") (pin "13") (pinfunction "I1_13") (pintype "input"))
      (node (ref "E17") (pin "6") (pinfunction "O_6") (pintype "output"))
    )
    (net (code "90") (name "Net-(E17C-I1)") (class "Default")
      (node (ref "E17") (pin "10") (pinfunction "I1_10") (pintype "input"))
      (node (ref "E17") (pin "11") (pinfunction "O_11") (pintype "output"))
    )
    (net (code "91") (name "Net-(E18A-CLK)") (class "Default")
      (node (ref "E18") (pin "3") (pinfunction "CLK_3") (pintype "input"))
      (node (ref "E9") (pin "4") (pinfunction "O_4") (pintype "output"))
    )
    (net (code "92") (name "Net-(E18A-CLR)") (class "Default")
      (node (ref "E18") (pin "1") (pinfunction "CLR_1") (pintype "input"))
      (node (ref "E26") (pin "13") (pinfunction "O_13") (pintype "output"))
      (node (ref "E9") (pin "5") (pinfunction "I_5") (pintype "input"))
    )
    (net (code "93") (name "Net-(E19A-PRE)") (class "Default")
      (node (ref "E19") (pin "4") (pinfunction "PRE_4") (pintype "input"))
      (node (ref "E26") (pin "1") (pinfunction "O_1") (pintype "output"))
    )
    (net (code "94") (name "Net-(E20A-CLR)") (class "Default")
      (node (ref "E20") (pin "1") (pinfunction "CLR_1") (pintype "input"))
      (node (ref "E26") (pin "4") (pinfunction "O_4") (pintype "output"))
    )
    (net (code "95") (name "Net-(E20B-CLR)") (class "Default")
      (node (ref "E20") (pin "13") (pinfunction "CLR_13") (pintype "input"))
      (node (ref "E29") (pin "10") (pinfunction "O_10") (pintype "output"))
    )
    (net (code "96") (name "Net-(E21A-CLR)") (class "Default")
      (node (ref "E21") (pin "1") (pinfunction "CLR_1") (pintype "input"))
      (node (ref "E23") (pin "1") (pinfunction "O_1") (pintype "output"))
    )
    (net (code "97") (name "Net-(E22A-CLR)") (class "Default")
      (node (ref "E22") (pin "1") (pinfunction "CLR_1") (pintype "input"))
      (node (ref "E23") (pin "10") (pinfunction "O_10") (pintype "output"))
    )
    (net (code "98") (name "Net-(E22B-CLK)") (class "Default")
      (node (ref "E22") (pin "11") (pinfunction "CLK_11") (pintype "input"))
      (node (ref "E32") (pin "3") (pinfunction "O_3") (pintype "output"))
    )
    (net (code "99") (name "Net-(E22B-CLR)") (class "Default")
      (node (ref "E22") (pin "13") (pinfunction "CLR_13") (pintype "input"))
      (node (ref "E23") (pin "13") (pinfunction "O_13") (pintype "output"))
    )
    (net (code "100") (name "Net-(E24A-CLR)") (class "Default")
      (node (ref "E24") (pin "1") (pinfunction "CLR_1") (pintype "input"))
      (node (ref "E29") (pin "1") (pinfunction "O_1") (pintype "output"))
    )
    (net (code "101") (name "Net-(E24B-CLR)") (class "Default")
      (node (ref "E24") (pin "13") (pinfunction "CLR_13") (pintype "input"))
      (node (ref "E29") (pin "4") (pinfunction "O_4") (pintype "output"))
    )
    (net (code "102") (name "Net-(E25A-I0)") (class "Default")
      (node (ref "E25") (pin "1") (pinfunction "I0_1") (pintype "input"))
      (node (ref "E25") (pin "8") (pinfunction "O_8") (pintype "output"))
    )
    (net (code "103") (name "Net-(E25A-O)") (class "Default")
      (node (ref "E25") (pin "3") (pinfunction "O_3") (pintype "output"))
      (node (ref "E9") (pin "3") (pinfunction "I_3") (pintype "input"))
    )
    (net (code "104") (name "Net-(E25B-O)") (class "Default")
      (node (ref "E25") (pin "6") (pinfunction "O_6") (pintype "output"))
      (node (ref "E26") (pin "11") (pinfunction "I0_11") (pintype "input"))
    )
    (net (code "105") (name "Net-(E26D-I1)") (class "Default")
      (node (ref "E26") (pin "12") (pinfunction "I1_12") (pintype "input"))
      (node (ref "E27") (pin "3") (pinfunction "O_3") (pintype "output"))
    )
    (net (code "106") (name "Net-(E27A-I0)") (class "Default")
      (node (ref "E27") (pin "1") (pinfunction "I0_1") (pintype "input"))
      (node (ref "E39") (pin "6") (pinfunction "O_6") (pintype "output"))
    )
    (net (code "107") (name "Net-(E29D-I0)") (class "Default")
      (node (ref "C39") (pin "1") (pinfunction "1_1") (pintype "passive"))
      (node (ref "E29") (pin "11") (pinfunction "I0_11") (pintype "input"))
      (node (ref "R18") (pin "2") (pinfunction "2_2") (pintype "passive"))
    )
    (net (code "108") (name "Net-(E30B-I0)") (class "Default")
      (node (ref "E30") (pin "13") (pinfunction "O_13") (pintype "output"))
      (node (ref "E30") (pin "5") (pinfunction "I0_5") (pintype "input"))
    )
    (net (code "109") (name "Net-(E30B-O)") (class "Default")
      (node (ref "E30") (pin "4") (pinfunction "O_4") (pintype "output"))
      (node (ref "E37") (pin "12") (pinfunction "D_12") (pintype "input"))
    )
    (net (code "110") (name "Net-(E32B-I1)") (class "Default")
      (node (ref "E32") (pin "11") (pinfunction "O_11") (pintype "output"))
      (node (ref "E32") (pin "5") (pinfunction "I1_5") (pintype "input"))
    )
    (net (code "111") (name "Net-(E33A-I1)") (class "Default")
      (node (ref "E33") (pin "2") (pinfunction "I1_2") (pintype "input"))
      (node (ref "E33") (pin "6") (pinfunction "O_6") (pintype "output"))
      (node (ref "E40") (pin "8") (pinfunction "I0_8") (pintype "input"))
    )
    (net (code "112") (name "Net-(E33A-O)") (class "Default")
      (node (ref "E33") (pin "3") (pinfunction "O_3") (pintype "output"))
      (node (ref "E34") (pin "2") (pinfunction "I1_2") (pintype "input"))
    )
    (net (code "113") (name "Net-(E33C-O)") (class "Default")
      (node (ref "E33") (pin "8") (pinfunction "O_8") (pintype "output"))
      (node (ref "E34") (pin "1") (pinfunction "I0_1") (pintype "input"))
    )
    (net (code "114") (name "Net-(E34A-O)") (class "Default")
      (node (ref "E34") (pin "12") (pinfunction "O_12") (pintype "output"))
      (node (ref "E34") (pin "5") (pinfunction "I2_5") (pintype "input"))
    )
    (net (code "115") (name "Net-(E36A-O)") (class "Default")
      (node (ref "E36") (pin "2") (pinfunction "O_2") (pintype "output"))
      (node (ref "E41") (pin "3") (pinfunction "CLK_3") (pintype "input"))
    )
    (net (code "116") (name "Net-(E36E-O)") (class "Default")
      (node (ref "E36") (pin "10") (pinfunction "O_10") (pintype "output"))
      (node (ref "R18") (pin "1") (pinfunction "1_1") (pintype "passive"))
    )
    (net (code "117") (name "Net-(E38A-C)") (class "Default")
      (node (ref "C33") (pin "1") (pinfunction "1_1") (pintype "passive"))
      (node (ref "E38") (pin "14") (pinfunction "C_14") (pintype "input"))
    )
    (net (code "118") (name "Net-(E38A-R{slash}C)") (class "Default")
      (node (ref "E38") (pin "15") (pinfunction "R/C_15") (pintype "input"))
      (node (ref "W1") (pin "2") (pinfunction "2_2") (pintype "passive"))
    )
    (net (code "119") (name "Net-(E38B-C)") (class "Default")
      (node (ref "C36") (pin "1") (pinfunction "1_1") (pintype "passive"))
      (node (ref "E38") (pin "6") (pinfunction "C_6") (pintype "input"))
    )
    (net (code "120") (name "Net-(E38B-R{slash}C)") (class "Default")
      (node (ref "E38") (pin "7") (pinfunction "R/C_7") (pintype "input"))
      (node (ref "W2") (pin "2") (pinfunction "2_2") (pintype "passive"))
    )
    (net (code "121") (name "Net-(E39A-O)") (class "Default")
      (node (ref "E39") (pin "12") (pinfunction "O_12") (pintype "output"))
      (node (ref "E45") (pin "12") (pinfunction "I0_12") (pintype "input"))
    )
    (net (code "122") (name "Net-(E39C-I2)") (class "Default")
      (node (ref "E39") (pin "11") (pinfunction "I2_11") (pintype "input"))
      (node (ref "E41") (pin "2") (pinfunction "D_2") (pintype "input"))
      (node (ref "E41") (pin "6") (pinfunction "~{Q}_6") (pintype "output"))
    )
    (net (code "123") (name "Net-(E40A-I0)") (class "Default")
      (node (ref "E40") (pin "10") (pinfunction "O_10") (pintype "output"))
      (node (ref "E40") (pin "2") (pinfunction "I0_2") (pintype "input"))
    )
    (net (code "124") (name "Net-(E43A-C)") (class "Default")
      (node (ref "C26") (pin "2") (pinfunction "2_2") (pintype "passive"))
      (node (ref "E43") (pin "14") (pinfunction "C_14") (pintype "input"))
    )
    (net (code "125") (name "Net-(E43A-R{slash}C)") (class "Default")
      (node (ref "D3") (pin "C") (pinfunction "C_C") (pintype "passive"))
      (node (ref "E43") (pin "15") (pinfunction "R/C_15") (pintype "input"))
    )
    (net (code "126") (name "Net-(E43B-C)") (class "Default")
      (node (ref "C31") (pin "1") (pinfunction "1_1") (pintype "passive"))
      (node (ref "E43") (pin "6") (pinfunction "C_6") (pintype "input"))
    )
    (net (code "127") (name "Net-(E43B-R{slash}C)") (class "Default")
      (node (ref "C31") (pin "2") (pinfunction "2_2") (pintype "passive"))
      (node (ref "E43") (pin "7") (pinfunction "R/C_7") (pintype "input"))
      (node (ref "R2") (pin "2") (pinfunction "2_2") (pintype "passive"))
    )
    (net (code "128") (name "Net-(E45A-I0)") (class "Default")
      (node (ref "E45") (pin "1") (pinfunction "I0_1") (pintype "input"))
      (node (ref "E51") (pin "3") (pinfunction "O_3") (pintype "output"))
    )
    (net (code "129") (name "Net-(E45A-O)") (class "Default")
      (node (ref "E45") (pin "3") (pinfunction "O_3") (pintype "output"))
      (node (ref "E45") (pin "4") (pinfunction "I0_4") (pintype "input"))
    )
    (net (code "130") (name "Net-(E45B-O)") (class "Default")
      (node (ref "E45") (pin "6") (pinfunction "O_6") (pintype "output"))
      (node (ref "E45") (pin "9") (pinfunction "I0_9") (pintype "input"))
    )
    (net (code "131") (name "Net-(E47A-A0)") (class "Default")
      (node (ref "E47") (pin "10") (pinfunction "A0_10") (pintype "input"))
      (node (ref "E53") (pin "14") (pinfunction "O_14") (pintype "output"))
    )
    (net (code "132") (name "Net-(E47A-A2)") (class "Default")
      (node (ref "E47") (pin "13") (pinfunction "A2_13") (pintype "input"))
      (node (ref "E53") (pin "3") (pinfunction "O_3") (pintype "output"))
    )
    (net (code "133") (name "Net-(E47A-A3)") (class "Default")
      (node (ref "E47") (pin "15") (pinfunction "A3_15") (pintype "input"))
      (node (ref "E53") (pin "2") (pinfunction "O_2") (pintype "output"))
    )
    (net (code "134") (name "Net-(E51A-I0)") (class "Default")
      (node (ref "C37") (pin "1") (pinfunction "1_1") (pintype "passive"))
      (node (ref "E51") (pin "13") (pinfunction "O_13") (pintype "output"))
      (node (ref "E51") (pin "4") (pinfunction "I0_4") (pintype "input"))
      (node (ref "E51") (pin "5") (pinfunction "I1_5") (pintype "input"))
      (node (ref "R17") (pin "2") (pinfunction "2_2") (pintype "passive"))
    )
    (net (code "135") (name "Net-(E51B-I0)") (class "Default")
      (node (ref "C37") (pin "2") (pinfunction "2_2") (pintype "passive"))
      (node (ref "E51") (pin "6") (pinfunction "I0_6") (pintype "input"))
      (node (ref "E51") (pin "7") (pinfunction "I1_7") (pintype "input"))
      (node (ref "R15") (pin "1") (pinfunction "1_1") (pintype "passive"))
    )
    (net (code "136") (name "Net-(E51B-O)") (class "Default")
      (node (ref "E51") (pin "2") (pinfunction "O_2") (pintype "output"))
      (node (ref "R14") (pin "2") (pinfunction "2_2") (pintype "passive"))
      (node (ref "R15") (pin "2") (pinfunction "2_2") (pintype "passive"))
    )
    (net (code "137") (name "Net-(E51C-O)") (class "Default")
      (node (ref "E51") (pin "14") (pinfunction "O_14") (pintype "output"))
      (node (ref "E54") (pin "7") (pinfunction "I1_7") (pintype "input"))
    )
    (net (code "138") (name "Net-(E51D-I0)") (class "Default")
      (node (ref "C38") (pin "1") (pinfunction "1_1") (pintype "passive"))
      (node (ref "E51") (pin "11") (pinfunction "I0_11") (pintype "input"))
      (node (ref "E51") (pin "12") (pinfunction "I1_12") (pintype "input"))
      (node (ref "R17") (pin "1") (pinfunction "1_1") (pintype "passive"))
    )
    (net (code "139") (name "Net-(J1AF-P)") (class "Default")
      (node (ref "J1") (pin "TT") (pinfunction "P_TT") (pintype "passive"))
      (node (ref "W3") (pin "2") (pinfunction "2_2") (pintype "passive"))
    )
    (net (code "140") (name "Net-(OMNIBUSBT-1)") (class "Default")
      (node (ref "OMNIBUS") (pin "BV2") (pinfunction "1_BV2") (pintype "bidirectional"))
      (node (ref "W3") (pin "1") (pinfunction "1_1") (pintype "passive"))
    )
    (net (code "141") (name "Net-(R4-E)") (class "Default")
      (node (ref "R4") (pin "2") (pinfunction "S_2") (pintype "passive"))
      (node (ref "R4") (pin "3") (pinfunction "E_3") (pintype "passive"))
      (node (ref "R5") (pin "2") (pinfunction "2_2") (pintype "passive"))
    )
    (net (code "142") (name "Net-(R12-E)") (class "Default")
      (node (ref "R12") (pin "2") (pinfunction "S_2") (pintype "passive"))
      (node (ref "R12") (pin "3") (pinfunction "E_3") (pintype "passive"))
      (node (ref "R13") (pin "2") (pinfunction "2_2") (pintype "passive"))
    )
    (net (code "143") (name "RDY_S{slash}R{slash}W") (class "Default")
      (node (ref "E") (pin "D1") (pinfunction "P_D1") (pintype "passive"))
      (node (ref "E16") (pin "1") (pinfunction "I0_1") (pintype "input"))
      (node (ref "E39") (pin "2") (pinfunction "I1_2") (pintype "input"))
    )
    (net (code "144") (name "RD_CLK1") (class "Default")
      (node (ref "E") (pin "B1") (pinfunction "P_B1") (pintype "passive"))
      (node (ref "E14") (pin "9") (pinfunction "I0_9") (pintype "input"))
      (node (ref "E7") (pin "8") (pinfunction "O_8") (pintype "output"))
    )
    (net (code "145") (name "RD_CLK2") (class "Default")
      (node (ref "E16") (pin "11") (pinfunction "O_11") (pintype "output"))
      (node (ref "E7") (pin "5") (pinfunction "I_5") (pintype "input"))
      (node (ref "E8") (pin "10") (pinfunction "I1_10") (pintype "input"))
    )
    (net (code "146") (name "RD_SHFT_CRC") (class "Default")
      (node (ref "E30") (pin "10") (pinfunction "O_10") (pintype "output"))
      (node (ref "E40") (pin "11") (pinfunction "I0_11") (pintype "input"))
    )
    (net (code "147") (name "READ") (class "Default")
      (node (ref "E15") (pin "1") (pinfunction "CLR_1") (pintype "input"))
      (node (ref "E37") (pin "8") (pinfunction "~{Q}_8") (pintype "output"))
      (node (ref "E49") (pin "1") (pinfunction "I0_1") (pintype "input"))
      (node (ref "E49") (pin "2") (pinfunction "I1_2") (pintype "input"))
      (node (ref "E8") (pin "1") (pinfunction "I0_1") (pintype "input"))
    )
    (net (code "148") (name "READ_CLK") (class "Default")
      (node (ref "E54") (pin "14") (pinfunction "O_14") (pintype "output"))
      (node (ref "E7") (pin "13") (pinfunction "I_13") (pintype "input"))
      (node (ref "E8") (pin "13") (pinfunction "I1_13") (pintype "input"))
    )
    (net (code "149") (name "READ_DATA_IN") (class "Default")
      (node (ref "E35") (pin "3") (pinfunction "I_3") (pintype "input"))
      (node (ref "E54") (pin "3") (pinfunction "O_3") (pintype "output"))
    )
    (net (code "150") (name "RESTORE") (class "Default")
      (node (ref "E18") (pin "9") (pinfunction "Q_9") (pintype "output"))
      (node (ref "E49") (pin "6") (pinfunction "I0_6") (pintype "input"))
      (node (ref "E49") (pin "7") (pinfunction "I1_7") (pintype "input"))
    )
    (net (code "151") (name "RK_DATA11") (class "Default")
      (node (ref "E28") (pin "4") (pinfunction "I4_4") (pintype "input"))
      (node (ref "E33") (pin "9") (pinfunction "I0_9") (pintype "input"))
      (node (ref "F") (pin "H1") (pinfunction "P_H1") (pintype "passive"))
    )
    (net (code "152") (name "SECTOR_ADDRS1") (class "Default")
      (node (ref "E") (pin "P2") (pinfunction "P_P2") (pintype "passive"))
      (node (ref "E46") (pin "10") (pinfunction "QE_10") (pintype "output"))
      (node (ref "E47") (pin "9") (pinfunction "B0_9") (pintype "input"))
    )
    (net (code "153") (name "SECTOR_ADDRS2") (class "Default")
      (node (ref "E46") (pin "11") (pinfunction "QD_11") (pintype "output"))
      (node (ref "E47") (pin "11") (pinfunction "B1_11") (pintype "input"))
    )
    (net (code "154") (name "SECTOR_ADDRS4") (class "Default")
      (node (ref "E46") (pin "13") (pinfunction "QC_13") (pintype "output"))
      (node (ref "E47") (pin "14") (pinfunction "B2_14") (pintype "input"))
    )
    (net (code "155") (name "SECTOR_ADDRS8") (class "Default")
      (node (ref "E46") (pin "14") (pinfunction "QB_14") (pintype "output"))
      (node (ref "E47") (pin "1") (pinfunction "B3_1") (pintype "input"))
    )
    (net (code "156") (name "SECTOR_EQ") (class "Default")
      (node (ref "E24") (pin "12") (pinfunction "D_12") (pintype "input"))
      (node (ref "E47") (pin "6") (pinfunction "A=B_O_6") (pintype "output"))
    )
    (net (code "157") (name "SECTOR_MK") (class "Default")
      (node (ref "E20") (pin "3") (pinfunction "CLK_3") (pintype "input"))
      (node (ref "E35") (pin "1") (pinfunction "I_1") (pintype "input"))
      (node (ref "E38") (pin "2") (pinfunction "B_2") (pintype "input"))
      (node (ref "E54") (pin "13") (pinfunction "O_13") (pintype "output"))
    )
    (net (code "158") (name "SECTOR_SEEK") (class "Default")
      (node (ref "E24") (pin "5") (pinfunction "Q_5") (pintype "output"))
      (node (ref "E29") (pin "9") (pinfunction "I1_9") (pintype "input"))
      (node (ref "E30") (pin "2") (pinfunction "I0_2") (pintype "input"))
      (node (ref "E47") (pin "3") (pinfunction "A=B_I_3") (pintype "input"))
    )
    (net (code "159") (name "SEEK_ONLY") (class "Default")
      (node (ref "E25") (pin "10") (pinfunction "I1_10") (pintype "input"))
      (node (ref "E25") (pin "11") (pinfunction "O_11") (pintype "output"))
    )
    (net (code "160") (name "SHFT_SURF") (class "Default")
      (node (ref "E46") (pin "1") (pinfunction "CLK_1") (pintype "input"))
      (node (ref "F") (pin "U1") (pinfunction "P_U1") (pintype "passive"))
    )
    (net (code "161") (name "STATE_ENAB_B") (class "Default")
      (node (ref "E13") (pin "3") (pinfunction "I1_3") (pintype "input"))
      (node (ref "E14") (pin "3") (pinfunction "O_3") (pintype "output"))
      (node (ref "E23") (pin "6") (pinfunction "I1_6") (pintype "input"))
      (node (ref "F") (pin "V1") (pinfunction "P_V1") (pintype "passive"))
    )
    (net (code "162") (name "STROBE") (class "Default")
      (node (ref "E") (pin "F2") (pinfunction "P_F2") (pintype "passive"))
      (node (ref "E19") (pin "9") (pinfunction "Q_9") (pintype "output"))
      (node (ref "E25") (pin "9") (pinfunction "I0_9") (pintype "input"))
      (node (ref "E48") (pin "1") (pinfunction "I0_1") (pintype "input"))
      (node (ref "E48") (pin "2") (pinfunction "I1_2") (pintype "input"))
    )
    (net (code "163") (name "TOP_SURF") (class "Default")
      (node (ref "E46") (pin "15") (pinfunction "QA_15") (pintype "output"))
      (node (ref "E48") (pin "6") (pinfunction "I0_6") (pintype "input"))
      (node (ref "E48") (pin "7") (pinfunction "I1_7") (pintype "input"))
    )
    (net (code "164") (name "VCC") (class "Default")
      (node (ref "C1") (pin "1") (pinfunction "1_1") (pintype "passive"))
      (node (ref "C10") (pin "1") (pinfunction "1_1") (pintype "passive"))
      (node (ref "C11") (pin "1") (pinfunction "1_1") (pintype "passive"))
      (node (ref "C12") (pin "1") (pinfunction "1_1") (pintype "passive"))
      (node (ref "C13") (pin "1") (pinfunction "1_1") (pintype "passive"))
      (node (ref "C14") (pin "1") (pinfunction "1_1") (pintype "passive"))
      (node (ref "C15") (pin "1") (pinfunction "1_1") (pintype "passive"))
      (node (ref "C16") (pin "1") (pinfunction "1_1") (pintype "passive"))
      (node (ref "C17") (pin "1") (pinfunction "1_1") (pintype "passive"))
      (node (ref "C18") (pin "1") (pinfunction "1_1") (pintype "passive"))
      (node (ref "C19") (pin "1") (pinfunction "1_1") (pintype "passive"))
      (node (ref "C2") (pin "1") (pinfunction "1_1") (pintype "passive"))
      (node (ref "C20") (pin "1") (pinfunction "1_1") (pintype "passive"))
      (node (ref "C21") (pin "1") (pinfunction "1_1") (pintype "passive"))
      (node (ref "C22") (pin "1") (pinfunction "1_1") (pintype "passive"))
      (node (ref "C23") (pin "1") (pinfunction "1_1") (pintype "passive"))
      (node (ref "C24") (pin "1") (pinfunction "1_1") (pintype "passive"))
      (node (ref "C25") (pin "1") (pinfunction "1_1") (pintype "passive"))
      (node (ref "C27") (pin "+") (pinfunction "+_+") (pintype "passive"))
      (node (ref "C28") (pin "+") (pinfunction "+_+") (pintype "passive"))
      (node (ref "C29") (pin "+") (pinfunction "+_+") (pintype "passive"))
      (node (ref "C3") (pin "1") (pinfunction "1_1") (pintype "passive"))
      (node (ref "C4") (pin "1") (pinfunction "1_1") (pintype "passive"))
      (node (ref "C41") (pin "1") (pinfunction "1_1") (pintype "passive"))
      (node (ref "C42") (pin "1") (pinfunction "1_1") (pintype "passive"))
      (node (ref "C43") (pin "1") (pinfunction "1_1") (pintype "passive"))
      (node (ref "C44") (pin "1") (pinfunction "1_1") (pintype "passive"))
      (node (ref "C5") (pin "1") (pinfunction "1_1") (pintype "passive"))
      (node (ref "C6") (pin "1") (pinfunction "1_1") (pintype "passive"))
      (node (ref "C7") (pin "1") (pinfunction "1_1") (pintype "passive"))
      (node (ref "C8") (pin "1") (pinfunction "1_1") (pintype "passive"))
      (node (ref "C9") (pin "1") (pinfunction "1_1") (pintype "passive"))
      (node (ref "OMNIBUS") (pin "AA2") (pinfunction "1_AA2") (pintype "bidirectional"))
      (node (ref "OMNIBUS") (pin "BA2") (pinfunction "1_BA2") (pintype "bidirectional"))
      (node (ref "OMNIBUS") (pin "CA2") (pinfunction "1_CA2") (pintype "bidirectional"))
      (node (ref "R10") (pin "2") (pinfunction "2_2") (pintype "passive"))
      (node (ref "R12") (pin "1") (pinfunction "A_1") (pintype "passive"))
      (node (ref "R19") (pin "2") (pinfunction "2_2") (pintype "passive"))
      (node (ref "R2") (pin "1") (pinfunction "1_1") (pintype "passive"))
      (node (ref "R21") (pin "2") (pinfunction "2_2") (pintype "passive"))
      (node (ref "R22") (pin "2") (pinfunction "2_2") (pintype "passive"))
      (node (ref "R24") (pin "2") (pinfunction "2_2") (pintype "passive"))
      (node (ref "R26") (pin "2") (pinfunction "2_2") (pintype "passive"))
      (node (ref "R28") (pin "2") (pinfunction "2_2") (pintype "passive"))
      (node (ref "R29") (pin "2") (pinfunction "2_2") (pintype "passive"))
      (node (ref "R32") (pin "2") (pinfunction "2_2") (pintype "passive"))
      (node (ref "R33") (pin "2") (pinfunction "2_2") (pintype "passive"))
      (node (ref "R36") (pin "2") (pinfunction "2_2") (pintype "passive"))
      (node (ref "R38") (pin "2") (pinfunction "2_2") (pintype "passive"))
      (node (ref "R4") (pin "1") (pinfunction "A_1") (pintype "passive"))
      (node (ref "R40") (pin "2") (pinfunction "2_2") (pintype "passive"))
      (node (ref "R42") (pin "2") (pinfunction "2_2") (pintype "passive"))
      (node (ref "R43") (pin "2") (pinfunction "2_2") (pintype "passive"))
      (node (ref "R46") (pin "2") (pinfunction "2_2") (pintype "passive"))
      (node (ref "R48") (pin "2") (pinfunction "2_2") (pintype "passive"))
      (node (ref "R50") (pin "2") (pinfunction "2_2") (pintype "passive"))
      (node (ref "R52") (pin "2") (pinfunction "2_2") (pintype "passive"))
      (node (ref "R54") (pin "2") (pinfunction "2_2") (pintype "passive"))
      (node (ref "R8") (pin "2") (pinfunction "2_2") (pintype "passive"))
      (node (ref "R9") (pin "2") (pinfunction "2_2") (pintype "passive"))
    )
    (net (code "165") (name "WRITE") (class "Default")
      (node (ref "E28") (pin "5") (pinfunction "I5_5") (pintype "input"))
      (node (ref "E39") (pin "9") (pinfunction "I0_9") (pintype "input"))
      (node (ref "E41") (pin "1") (pinfunction "CLR_1") (pintype "input"))
      (node (ref "E41") (pin "9") (pinfunction "Q_9") (pintype "output"))
      (node (ref "E45") (pin "10") (pinfunction "I1_10") (pintype "input"))
      (node (ref "E50") (pin "1") (pinfunction "I0_1") (pintype "input"))
      (node (ref "E50") (pin "2") (pinfunction "I1_2") (pintype "input"))
      (node (ref "F") (pin "F1") (pinfunction "P_F1") (pintype "passive"))
    )
    (net (code "166") (name "WRT_CLK_DATA") (class "Default")
      (node (ref "E27") (pin "11") (pinfunction "O_11") (pintype "output"))
      (node (ref "E44") (pin "1") (pinfunction "I0_1") (pintype "input"))
      (node (ref "E44") (pin "2") (pinfunction "I1_2") (pintype "input"))
    )
    (net (code "167") (name "WRT_CMD") (class "Default")
      (node (ref "E30") (pin "11") (pinfunction "I0_11") (pintype "input"))
      (node (ref "E33") (pin "11") (pinfunction "O_11") (pintype "output"))
      (node (ref "E36") (pin "5") (pinfunction "I_5") (pintype "input"))
      (node (ref "E38") (pin "10") (pinfunction "B_10") (pintype "input"))
      (node (ref "E41") (pin "12") (pinfunction "D_12") (pintype "input"))
    )
    (net (code "168") (name "WRT_LOCK_OUT") (class "Default")
      (node (ref "E35") (pin "6") (pinfunction "O_6") (pintype "output"))
      (node (ref "E50") (pin "7") (pinfunction "I1_7") (pintype "input"))
    )
    (net (code "169") (name "WRT_SHFT_CRC") (class "Default")
      (node (ref "E40") (pin "1") (pinfunction "O_1") (pintype "output"))
      (node (ref "E40") (pin "12") (pinfunction "I1_12") (pintype "input"))
    )
    (net (code "170") (name "WRT_SYNC_BIT") (class "Default")
      (node (ref "E27") (pin "10") (pinfunction "I1_10") (pintype "input"))
      (node (ref "E37") (pin "5") (pinfunction "Q_5") (pintype "output"))
    )
    (net (code "171") (name "unconnected-(E1A-QA-Pad14)") (class "Default")
      (node (ref "E1") (pin "14") (pinfunction "QA_14") (pintype "output"))
    )
    (net (code "172") (name "unconnected-(E1A-QB-Pad13)") (class "Default")
      (node (ref "E1") (pin "13") (pinfunction "QB_13") (pintype "output"))
    )
    (net (code "173") (name "unconnected-(E1A-QC-Pad12)") (class "Default")
      (node (ref "E1") (pin "12") (pinfunction "QC_12") (pintype "output"))
    )
    (net (code "174") (name "unconnected-(E1A-QD-Pad11)") (class "Default")
      (node (ref "E1") (pin "11") (pinfunction "QD_11") (pintype "output"))
    )
    (net (code "175") (name "unconnected-(E2A-QC-Pad12)") (class "Default")
      (node (ref "E2") (pin "12") (pinfunction "QC_12") (pintype "output"))
    )
    (net (code "176") (name "unconnected-(E2A-RCO-Pad15)") (class "Default")
      (node (ref "E2") (pin "15") (pinfunction "RCO_15") (pintype "output"))
    )
    (net (code "177") (name "unconnected-(E3A-QA-Pad14)") (class "Default")
      (node (ref "E3") (pin "14") (pinfunction "QA_14") (pintype "output"))
    )
    (net (code "178") (name "unconnected-(E3A-QB-Pad13)") (class "Default")
      (node (ref "E3") (pin "13") (pinfunction "QB_13") (pintype "output"))
    )
    (net (code "179") (name "unconnected-(E3A-QC-Pad12)") (class "Default")
      (node (ref "E3") (pin "12") (pinfunction "QC_12") (pintype "output"))
    )
    (net (code "180") (name "unconnected-(E3A-QD-Pad11)") (class "Default")
      (node (ref "E3") (pin "11") (pinfunction "QD_11") (pintype "output"))
    )
    (net (code "181") (name "unconnected-(E4A-QA-Pad14)") (class "Default")
      (node (ref "E4") (pin "14") (pinfunction "QA_14") (pintype "output"))
    )
    (net (code "182") (name "unconnected-(E4A-QB-Pad13)") (class "Default")
      (node (ref "E4") (pin "13") (pinfunction "QB_13") (pintype "output"))
    )
    (net (code "183") (name "unconnected-(E4A-QC-Pad12)") (class "Default")
      (node (ref "E4") (pin "12") (pinfunction "QC_12") (pintype "output"))
    )
    (net (code "184") (name "unconnected-(E5A-QA-Pad14)") (class "Default")
      (node (ref "E5") (pin "14") (pinfunction "QA_14") (pintype "output"))
    )
    (net (code "185") (name "unconnected-(E5A-QB-Pad13)") (class "Default")
      (node (ref "E5") (pin "13") (pinfunction "QB_13") (pintype "output"))
    )
    (net (code "186") (name "unconnected-(E5A-QC-Pad12)") (class "Default")
      (node (ref "E5") (pin "12") (pinfunction "QC_12") (pintype "output"))
    )
    (net (code "187") (name "unconnected-(E5A-QD-Pad11)") (class "Default")
      (node (ref "E5") (pin "11") (pinfunction "QD_11") (pintype "output"))
    )
    (net (code "188") (name "unconnected-(E6A-QA-Pad14)") (class "Default")
      (node (ref "E6") (pin "14") (pinfunction "QA_14") (pintype "output"))
    )
    (net (code "189") (name "unconnected-(E6A-QB-Pad13)") (class "Default")
      (node (ref "E6") (pin "13") (pinfunction "QB_13") (pintype "output"))
    )
    (net (code "190") (name "unconnected-(E6A-QC-Pad12)") (class "Default")
      (node (ref "E6") (pin "12") (pinfunction "QC_12") (pintype "output"))
    )
    (net (code "191") (name "unconnected-(E6A-QD-Pad11)") (class "Default")
      (node (ref "E6") (pin "11") (pinfunction "QD_11") (pintype "output"))
    )
    (net (code "192") (name "unconnected-(E19A-Q-Pad5)") (class "Default")
      (node (ref "E19") (pin "5") (pinfunction "Q_5") (pintype "output"))
    )
    (net (code "193") (name "unconnected-(E19B-~{Q}-Pad8)") (class "Default")
      (node (ref "E19") (pin "8") (pinfunction "~{Q}_8") (pintype "output"))
    )
    (net (code "194") (name "unconnected-(E20A-~{Q}-Pad6)") (class "Default")
      (node (ref "E20") (pin "6") (pinfunction "~{Q}_6") (pintype "output"))
    )
    (net (code "195") (name "unconnected-(E28A-I9-Pad9)") (class "Default")
      (node (ref "E28") (pin "9") (pinfunction "I9_9") (pintype "passive"))
    )
    (net (code "196") (name "unconnected-(E31A-1Y2-Pad5)") (class "Default")
      (node (ref "E31") (pin "5") (pinfunction "1Y2_5") (pintype "output"))
    )
    (net (code "197") (name "unconnected-(E31A-1Y3-Pad4)") (class "Default")
      (node (ref "E31") (pin "4") (pinfunction "1Y3_4") (pintype "output"))
    )
    (net (code "198") (name "unconnected-(E38A-Q-Pad13)") (class "Default")
      (node (ref "E38") (pin "13") (pinfunction "Q_13") (pintype "output"))
    )
    (net (code "199") (name "unconnected-(E38B-Q-Pad5)") (class "Default")
      (node (ref "E38") (pin "5") (pinfunction "Q_5") (pintype "output"))
    )
    (net (code "200") (name "unconnected-(E43A-Q-Pad13)") (class "Default")
      (node (ref "E43") (pin "13") (pinfunction "Q_13") (pintype "output"))
    )
    (net (code "201") (name "unconnected-(E43B-Q-Pad5)") (class "Default")
      (node (ref "E43") (pin "5") (pinfunction "Q_5") (pintype "output"))
    )
    (net (code "202") (name "unconnected-(E47A-A<B_O-Pad7)") (class "Default")
      (node (ref "E47") (pin "7") (pinfunction "A<B_O_7") (pintype "output"))
    )
    (net (code "203") (name "unconnected-(E47A-A>B_O-Pad5)") (class "Default")
      (node (ref "E47") (pin "5") (pinfunction "A>B_O_5") (pintype "output"))
    )
    (net (code "204") (name "~{6RK3_OK}") (class "Default")
      (node (ref "E13") (pin "9") (pinfunction "I1_9") (pintype "input"))
      (node (ref "E5") (pin "9") (pinfunction "LD_9") (pintype "input"))
      (node (ref "E6") (pin "9") (pinfunction "LD_9") (pintype "input"))
      (node (ref "E9") (pin "8") (pinfunction "O_8") (pintype "output"))
    )
    (net (code "205") (name "~{12TH_CARRY}") (class "Default")
      (node (ref "E10") (pin "8") (pinfunction "O_8") (pintype "output"))
      (node (ref "E11") (pin "5") (pinfunction "I_5") (pintype "input"))
      (node (ref "E2") (pin "9") (pinfunction "LD_9") (pintype "input"))
      (node (ref "R1") (pin "1") (pinfunction "1_1") (pintype "passive"))
    )
    (net (code "206") (name "~{16TH_BIT}") (class "Default")
      (node (ref "E11") (pin "11") (pinfunction "I_11") (pintype "input"))
      (node (ref "E12") (pin "11") (pinfunction "O_11") (pintype "output"))
      (node (ref "E21") (pin "11") (pinfunction "CLK_11") (pintype "input"))
      (node (ref "E22") (pin "3") (pinfunction "CLK_3") (pintype "input"))
    )
    (net (code "207") (name "~{B_WRT_CLK}") (class "Default")
      (node (ref "E10") (pin "2") (pinfunction "I1_2") (pintype "input"))
      (node (ref "E35") (pin "12") (pinfunction "O_12") (pintype "output"))
      (node (ref "E37") (pin "3") (pinfunction "CLK_3") (pintype "input"))
      (node (ref "E40") (pin "3") (pinfunction "I1_3") (pintype "input"))
      (node (ref "E40") (pin "6") (pinfunction "I1_6") (pintype "input"))
    )
    (net (code "208") (name "~{CHECK_HEADER_CMD}") (class "Default")
      (node (ref "E19") (pin "2") (pinfunction "D_2") (pintype "input"))
      (node (ref "E32") (pin "8") (pinfunction "O_8") (pintype "output"))
    )
    (net (code "209") (name "~{CLR_ALL}") (class "Default")
      (node (ref "E") (pin "H1") (pinfunction "P_H1") (pintype "passive"))
      (node (ref "E10") (pin "4") (pinfunction "I1_4") (pintype "input"))
      (node (ref "E16") (pin "5") (pinfunction "I1_5") (pintype "input"))
      (node (ref "E25") (pin "5") (pinfunction "I1_5") (pintype "input"))
      (node (ref "E5") (pin "1") (pinfunction "CLR_1") (pintype "input"))
      (node (ref "E6") (pin "1") (pinfunction "CLR_1") (pintype "input"))
    )
    (net (code "210") (name "~{CLR_CNTRS}") (class "Default")
      (node (ref "E1") (pin "1") (pinfunction "CLR_1") (pintype "input"))
      (node (ref "E11") (pin "4") (pinfunction "O_4") (pintype "output"))
      (node (ref "E15") (pin "10") (pinfunction "PRE_10") (pintype "input"))
      (node (ref "E2") (pin "1") (pinfunction "CLR_1") (pintype "input"))
      (node (ref "E3") (pin "1") (pinfunction "CLR_1") (pintype "input"))
      (node (ref "E4") (pin "1") (pinfunction "CLR_1") (pintype "input"))
      (node (ref "F") (pin "S1") (pinfunction "P_S1") (pintype "passive"))
    )
    (net (code "211") (name "~{CLR_DRIVE_CMD}") (class "Default")
      (node (ref "E45") (pin "13") (pinfunction "I1_13") (pintype "input"))
      (node (ref "E9") (pin "11") (pinfunction "I_11") (pintype "input"))
      (node (ref "F") (pin "B2") (pinfunction "P_B2") (pintype "passive"))
    )
    (net (code "212") (name "~{CLR_SECTOR_AD}") (class "Default")
      (node (ref "E") (pin "F1") (pinfunction "P_F1") (pintype "passive"))
      (node (ref "E46") (pin "16") (pinfunction "CLR_16") (pintype "input"))
    )
    (net (code "213") (name "~{CLR_STROBE}") (class "Default")
      (node (ref "E18") (pin "13") (pinfunction "CLR_13") (pintype "input"))
      (node (ref "E19") (pin "13") (pinfunction "CLR_13") (pintype "input"))
      (node (ref "E26") (pin "10") (pinfunction "O_10") (pintype "output"))
    )
    (net (code "214") (name "~{CRC_STATE}") (class "Default")
      (node (ref "E14") (pin "1") (pinfunction "I0_1") (pintype "input"))
      (node (ref "E21") (pin "4") (pinfunction "PRE_4") (pintype "input"))
      (node (ref "E21") (pin "6") (pinfunction "~{Q}_6") (pintype "output"))
      (node (ref "E33") (pin "5") (pinfunction "I1_5") (pintype "input"))
    )
    (net (code "215") (name "~{DATA8}") (class "Default")
      (node (ref "E52") (pin "6") (pinfunction "I0_6") (pintype "input"))
      (node (ref "OMNIBUS") (pin "DR1") (pinfunction "1_DR1") (pintype "bidirectional"))
    )
    (net (code "216") (name "~{DATA9}") (class "Default")
      (node (ref "E52") (pin "4") (pinfunction "I0_4") (pintype "input"))
      (node (ref "OMNIBUS") (pin "DS1") (pinfunction "1_DS1") (pintype "bidirectional"))
    )
    (net (code "217") (name "~{DATA10}") (class "Default")
      (node (ref "E52") (pin "9") (pinfunction "I0_9") (pintype "input"))
      (node (ref "OMNIBUS") (pin "DU1") (pinfunction "1_DU1") (pintype "bidirectional"))
    )
    (net (code "218") (name "~{DATA11}") (class "Default")
      (node (ref "E52") (pin "11") (pinfunction "I0_11") (pintype "input"))
      (node (ref "OMNIBUS") (pin "DV1") (pinfunction "1_DV1") (pintype "bidirectional"))
    )
    (net (code "219") (name "~{DATA_CLR}") (class "Default")
      (node (ref "E10") (pin "5") (pinfunction "I2_5") (pintype "input"))
      (node (ref "E43") (pin "12") (pinfunction "~{Q}_12") (pintype "output"))
    )
    (net (code "220") (name "~{DATA_ENAB}") (class "Default")
      (node (ref "E") (pin "V1") (pinfunction "P_V1") (pintype "passive"))
      (node (ref "E52") (pin "10") (pinfunction "I1_10") (pintype "input"))
      (node (ref "E52") (pin "12") (pinfunction "I1_12") (pintype "input"))
      (node (ref "E52") (pin "5") (pinfunction "I1_5") (pintype "input"))
      (node (ref "E52") (pin "7") (pinfunction "I1_7") (pintype "input"))
    )
    (net (code "221") (name "~{DATA_IN}") (class "Default")
      (node (ref "E15") (pin "6") (pinfunction "~{Q}_6") (pintype "output"))
      (node (ref "F") (pin "R1") (pinfunction "P_R1") (pintype "passive"))
    )
    (net (code "222") (name "~{DATA_OUT_PL}") (class "Default")
      (node (ref "E27") (pin "13") (pinfunction "I1_13") (pintype "input"))
      (node (ref "E34") (pin "6") (pinfunction "O_6") (pintype "output"))
    )
    (net (code "223") (name "~{DATA_STATE}") (class "Default")
      (node (ref "E22") (pin "4") (pinfunction "PRE_4") (pintype "input"))
      (node (ref "E22") (pin "6") (pinfunction "~{Q}_6") (pintype "output"))
      (node (ref "E40") (pin "5") (pinfunction "I0_5") (pintype "input"))
      (node (ref "F") (pin "P1") (pinfunction "P_P1") (pintype "passive"))
    )
    (net (code "224") (name "~{DSK_ACKNOWLEDGE}") (class "Default")
      (node (ref "E16") (pin "2") (pinfunction "I1_2") (pintype "input"))
      (node (ref "E42") (pin "7") (pinfunction "I1_7") (pintype "input"))
      (node (ref "J2") (pin "H") (pinfunction "P_H") (pintype "passive"))
      (node (ref "R24") (pin "1") (pinfunction "1_1") (pintype "passive"))
      (node (ref "R25") (pin "2") (pinfunction "2_2") (pintype "passive"))
    )
    (net (code "225") (name "~{DSK_CAPACITY_EX}") (class "Default")
      (node (ref "F") (pin "C1") (pinfunction "P_C1") (pintype "passive"))
      (node (ref "J2") (pin "C") (pinfunction "P_C") (pintype "passive"))
    )
    (net (code "226") (name "~{DSK_CYL_AD1}") (class "Default")
      (node (ref "E") (pin "S1") (pinfunction "P_S1") (pintype "passive"))
      (node (ref "J2") (pin "Y") (pinfunction "P_Y") (pintype "passive"))
    )
    (net (code "227") (name "~{DSK_CYL_AD2}") (class "Default")
      (node (ref "E") (pin "K2") (pinfunction "P_K2") (pintype "passive"))
      (node (ref "J2") (pin "SS") (pinfunction "P_SS") (pintype "passive"))
    )
    (net (code "228") (name "~{DSK_CYL_AD4}") (class "Default")
      (node (ref "E") (pin "H2") (pinfunction "P_H2") (pintype "passive"))
      (node (ref "J2") (pin "U") (pinfunction "P_U") (pintype "passive"))
    )
    (net (code "229") (name "~{DSK_CYL_AD8}") (class "Default")
      (node (ref "E") (pin "T1") (pinfunction "P_T1") (pintype "passive"))
      (node (ref "J2") (pin "UU") (pinfunction "P_UU") (pintype "passive"))
    )
    (net (code "230") (name "~{DSK_CYL_AD16}") (class "Default")
      (node (ref "E") (pin "C2") (pinfunction "P_C2") (pintype "passive"))
      (node (ref "J2") (pin "MM") (pinfunction "P_MM") (pintype "passive"))
    )
    (net (code "231") (name "~{DSK_CYL_AD32}") (class "Default")
      (node (ref "E") (pin "J2") (pinfunction "P_J2") (pintype "passive"))
      (node (ref "J2") (pin "CC") (pinfunction "P_CC") (pintype "passive"))
    )
    (net (code "232") (name "~{DSK_CYL_AD64}") (class "Default")
      (node (ref "E") (pin "B2") (pinfunction "P_B2") (pintype "passive"))
      (node (ref "J2") (pin "PP") (pinfunction "P_PP") (pintype "passive"))
    )
    (net (code "233") (name "~{DSK_CYL_AD128}") (class "Default")
      (node (ref "E") (pin "E2") (pinfunction "P_E2") (pintype "passive"))
      (node (ref "J2") (pin "HH") (pinfunction "P_HH") (pintype "passive"))
    )
    (net (code "234") (name "~{DSK_DATA_IN}") (class "Default")
      (node (ref "E54") (pin "5") (pinfunction "I1_5") (pintype "input"))
      (node (ref "J1") (pin "D") (pinfunction "P_D") (pintype "passive"))
      (node (ref "R31") (pin "2") (pinfunction "2_2") (pintype "passive"))
      (node (ref "R32") (pin "1") (pinfunction "1_1") (pintype "passive"))
    )
    (net (code "235") (name "~{DSK_DRIVE0}") (class "Default")
      (node (ref "E") (pin "D2") (pinfunction "P_D2") (pintype "passive"))
      (node (ref "J2") (pin "AA") (pinfunction "P_AA") (pintype "passive"))
    )
    (net (code "236") (name "~{DSK_DRIVE1}") (class "Default")
      (node (ref "E") (pin "R1") (pinfunction "P_R1") (pintype "passive"))
      (node (ref "J2") (pin "W") (pinfunction "P_W") (pintype "passive"))
    )
    (net (code "237") (name "~{DSK_DRIVE2}") (class "Default")
      (node (ref "E") (pin "P1") (pinfunction "P_P1") (pintype "passive"))
      (node (ref "J2") (pin "S") (pinfunction "P_S") (pintype "passive"))
    )
    (net (code "238") (name "~{DSK_DRIVE3}") (class "Default")
      (node (ref "E") (pin "N1") (pinfunction "P_N1") (pintype "passive"))
      (node (ref "J2") (pin "M") (pinfunction "P_M") (pintype "passive"))
    )
    (net (code "239") (name "~{DSK_FILE_RDY}") (class "Default")
      (node (ref "E54") (pin "6") (pinfunction "I0_6") (pintype "input"))
      (node (ref "F") (pin "B1") (pinfunction "P_B1") (pintype "passive"))
      (node (ref "J1") (pin "V") (pinfunction "P_V") (pintype "passive"))
      (node (ref "R33") (pin "1") (pinfunction "1_1") (pintype "passive"))
      (node (ref "R34") (pin "2") (pinfunction "2_2") (pintype "passive"))
    )
    (net (code "240") (name "~{DSK_HEAD_SEL1}") (class "Default")
      (node (ref "E48") (pin "5") (pinfunction "O_5") (pintype "open_collector"))
      (node (ref "J1") (pin "X") (pinfunction "P_X") (pintype "passive"))
      (node (ref "R47") (pin "2") (pinfunction "2_2") (pintype "passive"))
      (node (ref "R48") (pin "1") (pinfunction "1_1") (pintype "passive"))
    )
    (net (code "241") (name "~{DSK_INDEX_MK}") (class "Default")
      (node (ref "E53") (pin "11") (pinfunction "I0_11") (pintype "input"))
      (node (ref "J1") (pin "Z") (pinfunction "P_Z") (pintype "passive"))
      (node (ref "R41") (pin "2") (pinfunction "2_2") (pintype "passive"))
      (node (ref "R42") (pin "1") (pinfunction "1_1") (pintype "passive"))
    )
    (net (code "242") (name "~{DSK_RDY_S-R-W}") (class "Default")
      (node (ref "E") (pin "L2") (pinfunction "P_L2") (pintype "passive"))
      (node (ref "J2") (pin "EE") (pinfunction "P_EE") (pintype "passive"))
    )
    (net (code "243") (name "~{DSK_RD_CLK}") (class "Default")
      (node (ref "E54") (pin "9") (pinfunction "I0_9") (pintype "input"))
      (node (ref "J1") (pin "F") (pinfunction "P_F") (pintype "passive"))
      (node (ref "R29") (pin "1") (pinfunction "1_1") (pintype "passive"))
      (node (ref "R30") (pin "2") (pinfunction "2_2") (pintype "passive"))
    )
    (net (code "244") (name "~{DSK_READ}") (class "Default")
      (node (ref "E49") (pin "3") (pinfunction "O_3") (pintype "open_collector"))
      (node (ref "J1") (pin "L") (pinfunction "P_L") (pintype "passive"))
      (node (ref "R45") (pin "2") (pinfunction "2_2") (pintype "passive"))
      (node (ref "R46") (pin "1") (pinfunction "1_1") (pintype "passive"))
    )
    (net (code "245") (name "~{DSK_RESTORE}") (class "Default")
      (node (ref "E49") (pin "5") (pinfunction "O_5") (pintype "open_collector"))
      (node (ref "J2") (pin "P") (pinfunction "P_P") (pintype "passive"))
      (node (ref "R20") (pin "2") (pinfunction "2_2") (pintype "passive"))
      (node (ref "R21") (pin "1") (pinfunction "1_1") (pintype "passive"))
    )
    (net (code "246") (name "~{DSK_SEC1}") (class "Default")
      (node (ref "E53") (pin "9") (pinfunction "I0_9") (pintype "input"))
      (node (ref "J1") (pin "DD") (pinfunction "P_DD") (pintype "passive"))
      (node (ref "R39") (pin "2") (pinfunction "2_2") (pintype "passive"))
      (node (ref "R40") (pin "1") (pinfunction "1_1") (pintype "passive"))
    )
    (net (code "247") (name "~{DSK_SEC2}") (class "Default")
      (node (ref "E42") (pin "4") (pinfunction "I0_4") (pintype "input"))
      (node (ref "J2") (pin "K") (pinfunction "P_K") (pintype "passive"))
      (node (ref "R22") (pin "1") (pinfunction "1_1") (pintype "passive"))
      (node (ref "R23") (pin "2") (pinfunction "2_2") (pintype "passive"))
    )
    (net (code "248") (name "~{DSK_SEC4}") (class "Default")
      (node (ref "E53") (pin "4") (pinfunction "I0_4") (pintype "input"))
      (node (ref "J1") (pin "FF") (pinfunction "P_FF") (pintype "passive"))
      (node (ref "R37") (pin "2") (pinfunction "2_2") (pintype "passive"))
      (node (ref "R38") (pin "1") (pinfunction "1_1") (pintype "passive"))
    )
    (net (code "249") (name "~{DSK_SEC8}") (class "Default")
      (node (ref "E53") (pin "6") (pinfunction "I0_6") (pintype "input"))
      (node (ref "J1") (pin "LL") (pinfunction "P_LL") (pintype "passive"))
      (node (ref "R35") (pin "2") (pinfunction "2_2") (pintype "passive"))
      (node (ref "R36") (pin "1") (pinfunction "1_1") (pintype "passive"))
    )
    (net (code "250") (name "~{DSK_SECTOR_MK}") (class "Default")
      (node (ref "E54") (pin "12") (pinfunction "I1_12") (pintype "input"))
      (node (ref "J1") (pin "T") (pinfunction "P_T") (pintype "passive"))
      (node (ref "R27") (pin "2") (pinfunction "2_2") (pintype "passive"))
      (node (ref "R28") (pin "1") (pinfunction "1_1") (pintype "passive"))
    )
    (net (code "251") (name "~{DSK_SEEK_FAIL}") (class "Default")
      (node (ref "E") (pin "A2") (pinfunction "P_A2") (pintype "passive"))
      (node (ref "J2") (pin "E") (pinfunction "P_E") (pintype "passive"))
    )
    (net (code "252") (name "~{DSK_STROBE}") (class "Default")
      (node (ref "E48") (pin "3") (pinfunction "O_3") (pintype "open_collector"))
      (node (ref "J1") (pin "RR") (pinfunction "P_RR") (pintype "passive"))
      (node (ref "R49") (pin "2") (pinfunction "2_2") (pintype "passive"))
      (node (ref "R50") (pin "1") (pinfunction "1_1") (pintype "passive"))
    )
    (net (code "253") (name "~{DSK_WRT-ERASE_GATE}") (class "Default")
      (node (ref "E50") (pin "3") (pinfunction "O_3") (pintype "open_collector"))
      (node (ref "J1") (pin "BB") (pinfunction "P_BB") (pintype "passive"))
      (node (ref "R53") (pin "2") (pinfunction "2_2") (pintype "passive"))
      (node (ref "R54") (pin "1") (pinfunction "1_1") (pintype "passive"))
    )
    (net (code "254") (name "~{DSK_WRT_CLK_DATA}") (class "Default")
      (node (ref "E44") (pin "3") (pinfunction "O_3") (pintype "open_collector"))
      (node (ref "J2") (pin "KK") (pinfunction "P_KK") (pintype "passive"))
      (node (ref "R10") (pin "1") (pinfunction "1_1") (pintype "passive"))
      (node (ref "R11") (pin "2") (pinfunction "2_2") (pintype "passive"))
    )
    (net (code "255") (name "~{DSK_WRT_PROTECT}") (class "Default")
      (node (ref "E50") (pin "5") (pinfunction "O_5") (pintype "open_collector"))
      (node (ref "J1") (pin "J") (pinfunction "P_J") (pintype "passive"))
      (node (ref "R51") (pin "2") (pinfunction "2_2") (pintype "passive"))
      (node (ref "R52") (pin "1") (pinfunction "1_1") (pintype "passive"))
    )
    (net (code "256") (name "~{DSK_WRT_STATUS}") (class "Default")
      (node (ref "E51") (pin "10") (pinfunction "I1_10") (pintype "input"))
      (node (ref "F") (pin "D2") (pinfunction "P_D2") (pintype "passive"))
      (node (ref "J1") (pin "R") (pinfunction "P_R") (pintype "passive"))
    )
    (net (code "257") (name "~{END_STATE}") (class "Default")
      (node (ref "E21") (pin "8") (pinfunction "~{Q}_8") (pintype "output"))
      (node (ref "F") (pin "D1") (pinfunction "P_D1") (pintype "passive"))
    )
    (net (code "258") (name "~{ERASE_DLY}") (class "Default")
      (node (ref "E25") (pin "2") (pinfunction "I1_2") (pintype "input"))
      (node (ref "E43") (pin "4") (pinfunction "~{Q}_4") (pintype "output"))
    )
    (net (code "259") (name "~{ERROR_CLR}") (class "Default")
      (node (ref "E25") (pin "4") (pinfunction "I0_4") (pintype "input"))
      (node (ref "F") (pin "E2") (pinfunction "P_E2") (pintype "passive"))
    )
    (net (code "260") (name "~{GO}") (class "Default")
      (node (ref "E18") (pin "4") (pinfunction "PRE_4") (pintype "input"))
      (node (ref "E9") (pin "2") (pinfunction "O_2") (pintype "output"))
    )
    (net (code "261") (name "~{HEADER_C}") (class "Default")
      (node (ref "E14") (pin "2") (pinfunction "I1_2") (pintype "input"))
      (node (ref "E20") (pin "10") (pinfunction "PRE_10") (pintype "input"))
      (node (ref "E20") (pin "8") (pinfunction "~{Q}_8") (pintype "output"))
    )
    (net (code "262") (name "~{HEADER_D}") (class "Default")
      (node (ref "E24") (pin "8") (pinfunction "~{Q}_8") (pintype "output"))
      (node (ref "E30") (pin "12") (pinfunction "I1_12") (pintype "input"))
    )
    (net (code "263") (name "~{HEADER_E}") (class "Default")
      (node (ref "E22") (pin "10") (pinfunction "PRE_10") (pintype "input"))
      (node (ref "E22") (pin "8") (pinfunction "~{Q}_8") (pintype "output"))
      (node (ref "E33") (pin "4") (pinfunction "I0_4") (pintype "input"))
    )
    (net (code "264") (name "~{HI_MAIN_SHFT}") (class "Default")
      (node (ref "E10") (pin "13") (pinfunction "I2_13") (pintype "input"))
      (node (ref "F") (pin "T2") (pinfunction "P_T2") (pintype "passive"))
    )
    (net (code "265") (name "~{IDLE}") (class "Default")
      (node (ref "E18") (pin "5") (pinfunction "Q_5") (pintype "output"))
      (node (ref "E21") (pin "13") (pinfunction "CLR_13") (pintype "input"))
      (node (ref "E35") (pin "11") (pinfunction "I_11") (pintype "input"))
      (node (ref "E41") (pin "13") (pinfunction "CLR_13") (pintype "input"))
      (node (ref "F") (pin "R2") (pinfunction "P_R2") (pintype "passive"))
    )
    (net (code "266") (name "~{INC_BRK_CNTR}") (class "Default")
      (node (ref "E13") (pin "4") (pinfunction "O_4") (pintype "output"))
      (node (ref "E5") (pin "2") (pinfunction "CLK_2") (pintype "input"))
      (node (ref "E6") (pin "2") (pinfunction "CLK_2") (pintype "input"))
    )
    (net (code "267") (name "~{INC_CNTRS}") (class "Default")
      (node (ref "E1") (pin "2") (pinfunction "CLK_2") (pintype "input"))
      (node (ref "E11") (pin "2") (pinfunction "O_2") (pintype "output"))
      (node (ref "E2") (pin "2") (pinfunction "CLK_2") (pintype "input"))
      (node (ref "E3") (pin "2") (pinfunction "CLK_2") (pintype "input"))
      (node (ref "E4") (pin "2") (pinfunction "CLK_2") (pintype "input"))
    )
    (net (code "268") (name "~{INH_12TH_BIT}") (class "Default")
      (node (ref "E14") (pin "12") (pinfunction "I0_12") (pintype "input"))
      (node (ref "E15") (pin "9") (pinfunction "Q_9") (pintype "output"))
      (node (ref "E17") (pin "12") (pinfunction "I0_12") (pintype "input"))
    )
    (net (code "269") (name "~{INSIDE_IN}") (class "Default")
      (node (ref "E45") (pin "2") (pinfunction "I1_2") (pintype "input"))
      (node (ref "OMNIBUS") (pin "DA1") (pinfunction "1_DA1") (pintype "bidirectional"))
      (node (ref "R9") (pin "1") (pinfunction "1_1") (pintype "passive"))
      (node (ref "TP2") (pin "P$1") (pinfunction "P_P$1") (pintype "passive"))
    )
    (net (code "270") (name "~{LAST_WORD_PL}") (class "Default")
      (node (ref "E11") (pin "9") (pinfunction "I_9") (pintype "input"))
      (node (ref "E12") (pin "8") (pinfunction "O_8") (pintype "output"))
      (node (ref "E21") (pin "3") (pinfunction "CLK_3") (pintype "input"))
    )
    (net (code "271") (name "~{LO_MAIN_SHFT}") (class "Default")
      (node (ref "E17") (pin "9") (pinfunction "I0_9") (pintype "input"))
      (node (ref "F") (pin "L1") (pinfunction "P_L1") (pintype "passive"))
    )
    (net (code "272") (name "~{MA0}") (class "Default")
      (node (ref "OMNIBUS") (pin "AD1") (pinfunction "1_AD1") (pintype "bidirectional"))
      (node (ref "SV14") (pin "1") (pinfunction "1_1") (pintype "passive"))
    )
    (net (code "273") (name "~{MA1}") (class "Default")
      (node (ref "OMNIBUS") (pin "AE1") (pinfunction "1_AE1") (pintype "bidirectional"))
      (node (ref "SV13") (pin "1") (pinfunction "1_1") (pintype "passive"))
    )
    (net (code "274") (name "~{MA3}") (class "Default")
      (node (ref "OMNIBUS") (pin "AJ1") (pinfunction "1_AJ1") (pintype "bidirectional"))
      (node (ref "SV12") (pin "1") (pinfunction "1_1") (pintype "passive"))
    )
    (net (code "275") (name "~{MA10}") (class "Default")
      (node (ref "OMNIBUS") (pin "DH1") (pinfunction "1_DH1") (pintype "bidirectional"))
      (node (ref "SV6") (pin "1") (pinfunction "1_1") (pintype "passive"))
    )
    (net (code "276") (name "~{MA11}") (class "Default")
      (node (ref "OMNIBUS") (pin "DJ1") (pinfunction "1_DJ1") (pintype "bidirectional"))
      (node (ref "SV5") (pin "1") (pinfunction "1_1") (pintype "passive"))
    )
    (net (code "277") (name "~{MAIN}") (class "Default")
      (node (ref "E39") (pin "13") (pinfunction "I2_13") (pintype "input"))
      (node (ref "F") (pin "P2") (pinfunction "P_P2") (pintype "passive"))
    )
    (net (code "278") (name "~{MD0}") (class "Default")
      (node (ref "OMNIBUS") (pin "AK1") (pinfunction "1_AK1") (pintype "bidirectional"))
      (node (ref "SV11") (pin "1") (pinfunction "1_1") (pintype "passive"))
    )
    (net (code "279") (name "~{MD1}") (class "Default")
      (node (ref "OMNIBUS") (pin "AL1") (pinfunction "1_AL1") (pintype "bidirectional"))
      (node (ref "SV10") (pin "1") (pinfunction "1_1") (pintype "passive"))
    )
    (net (code "280") (name "~{MD2}") (class "Default")
      (node (ref "OMNIBUS") (pin "AM1") (pinfunction "1_AM1") (pintype "bidirectional"))
      (node (ref "SV9") (pin "1") (pinfunction "1_1") (pintype "passive"))
    )
    (net (code "281") (name "~{MD8}") (class "Default")
      (node (ref "OMNIBUS") (pin "DK1") (pinfunction "1_DK1") (pintype "bidirectional"))
      (node (ref "SV4") (pin "1") (pinfunction "1_1") (pintype "passive"))
    )
    (net (code "282") (name "~{MD9}") (class "Default")
      (node (ref "OMNIBUS") (pin "DL1") (pinfunction "1_DL1") (pintype "bidirectional"))
      (node (ref "SV3") (pin "1") (pinfunction "1_1") (pintype "passive"))
    )
    (net (code "283") (name "~{MD10}") (class "Default")
      (node (ref "OMNIBUS") (pin "DM1") (pinfunction "1_DM1") (pintype "bidirectional"))
      (node (ref "SV2") (pin "1") (pinfunction "1_1") (pintype "passive"))
    )
    (net (code "284") (name "~{MD11}") (class "Default")
      (node (ref "OMNIBUS") (pin "DP1") (pinfunction "1_DP1") (pintype "bidirectional"))
      (node (ref "SV1") (pin "1") (pinfunction "1_1") (pintype "passive"))
    )
    (net (code "285") (name "~{OUTSIDE_CLK}") (class "Default")
      (node (ref "E45") (pin "5") (pinfunction "I1_5") (pintype "input"))
      (node (ref "OMNIBUS") (pin "DB1") (pinfunction "1_DB1") (pintype "bidirectional"))
      (node (ref "R8") (pin "1") (pinfunction "1_1") (pintype "passive"))
      (node (ref "TP3") (pin "P$1") (pinfunction "P_P$1") (pintype "passive"))
    )
    (net (code "286") (name "~{RD_CLK1}") (class "Default")
      (node (ref "E16") (pin "12") (pinfunction "I0_12") (pintype "input"))
      (node (ref "E30") (pin "8") (pinfunction "I0_8") (pintype "input"))
      (node (ref "E7") (pin "11") (pinfunction "I_11") (pintype "input"))
      (node (ref "E7") (pin "9") (pinfunction "I_9") (pintype "input"))
      (node (ref "E8") (pin "11") (pinfunction "O_11") (pintype "output"))
    )
    (net (code "287") (name "~{RD_CLK2}") (class "Default")
      (node (ref "E10") (pin "1") (pinfunction "I0_1") (pintype "input"))
      (node (ref "E15") (pin "3") (pinfunction "CLK_3") (pintype "input"))
      (node (ref "E7") (pin "6") (pinfunction "O_6") (pintype "output"))
    )
    (net (code "288") (name "~{RD_SHFT_DB}") (class "Default")
      (node (ref "E14") (pin "8") (pinfunction "O_8") (pintype "output"))
      (node (ref "F") (pin "S2") (pinfunction "P_S2") (pintype "passive"))
    )
    (net (code "289") (name "~{RD_SYNC_BIT}") (class "Default")
      (node (ref "E20") (pin "11") (pinfunction "CLK_11") (pintype "input"))
      (node (ref "E32") (pin "2") (pinfunction "I1_2") (pintype "input"))
      (node (ref "E8") (pin "8") (pinfunction "O_8") (pintype "output"))
    )
    (net (code "290") (name "~{READ_DATA_IN}") (class "Default")
      (node (ref "E15") (pin "4") (pinfunction "PRE_4") (pintype "input"))
      (node (ref "E35") (pin "4") (pinfunction "O_4") (pintype "output"))
    )
    (net (code "291") (name "~{READ_DLY}") (class "Default")
      (node (ref "E37") (pin "11") (pinfunction "CLK_11") (pintype "input"))
      (node (ref "E38") (pin "4") (pinfunction "~{Q}_4") (pintype "output"))
    )
    (net (code "292") (name "~{READ}") (class "Default")
      (node (ref "E37") (pin "9") (pinfunction "Q_9") (pintype "output"))
      (node (ref "E54") (pin "10") (pinfunction "I1_10") (pintype "input"))
      (node (ref "E54") (pin "4") (pinfunction "I0_4") (pintype "input"))
    )
    (net (code "293") (name "~{RESTORE}") (class "Default")
      (node (ref "E18") (pin "8") (pinfunction "~{Q}_8") (pintype "output"))
      (node (ref "E25") (pin "13") (pinfunction "I1_13") (pintype "input"))
    )
    (net (code "294") (name "~{SECTOR_MK}") (class "Default")
      (node (ref "E24") (pin "11") (pinfunction "CLK_11") (pintype "input"))
      (node (ref "E35") (pin "2") (pinfunction "O_2") (pintype "output"))
      (node (ref "E38") (pin "9") (pinfunction "A_9") (pintype "input"))
    )
    (net (code "295") (name "~{SECTOR_SEEK}") (class "Default")
      (node (ref "E24") (pin "6") (pinfunction "~{Q}_6") (pintype "output"))
      (node (ref "F") (pin "F2") (pinfunction "P_F2") (pintype "passive"))
    )
    (net (code "296") (name "~{SEEK}") (class "Default")
      (node (ref "E25") (pin "12") (pinfunction "I0_12") (pintype "input"))
      (node (ref "E31") (pin "12") (pinfunction "2Y3_12") (pintype "output"))
    )
    (net (code "297") (name "~{SET_HEADER_E}") (class "Default")
      (node (ref "E27") (pin "8") (pinfunction "O_8") (pintype "output"))
      (node (ref "E32") (pin "1") (pinfunction "I0_1") (pintype "input"))
    )
    (net (code "298") (name "~{SET_IDLE_PL}") (class "Default")
      (node (ref "E27") (pin "2") (pinfunction "I1_2") (pintype "input"))
      (node (ref "F") (pin "K1") (pinfunction "P_K1") (pintype "passive"))
    )
    (net (code "299") (name "~{SET_SECTOR_SEEK}") (class "Default")
      (node (ref "E24") (pin "4") (pinfunction "PRE_4") (pintype "input"))
      (node (ref "E27") (pin "6") (pinfunction "O_6") (pintype "output"))
    )
    (net (code "300") (name "~{SHFT_WRT_BUFF}") (class "Default")
      (node (ref "E14") (pin "11") (pinfunction "O_11") (pintype "output"))
      (node (ref "F") (pin "J2") (pinfunction "P_J2") (pintype "passive"))
    )
    (net (code "301") (name "~{SHIFT_CRC}") (class "Default")
      (node (ref "E40") (pin "13") (pinfunction "O_13") (pintype "output"))
      (node (ref "F") (pin "N1") (pinfunction "P_N1") (pintype "passive"))
    )
    (net (code "302") (name "~{SKIP}") (class "Default")
      (node (ref "OMNIBUS") (pin "CS1") (pinfunction "1_CS1") (pintype "bidirectional"))
      (node (ref "SV7") (pin "1") (pinfunction "1_1") (pintype "passive"))
    )
    (net (code "303") (name "~{SK{slash}CHK{slash}RD}") (class "Default")
      (node (ref "E31") (pin "9") (pinfunction "2Y0_9") (pintype "output"))
      (node (ref "E32") (pin "9") (pinfunction "I0_9") (pintype "input"))
    )
    (net (code "304") (name "~{SK{slash}CHK{slash}WRT}") (class "Default")
      (node (ref "E31") (pin "7") (pinfunction "1Y0_7") (pintype "output"))
      (node (ref "E32") (pin "10") (pinfunction "I1_10") (pintype "input"))
      (node (ref "E33") (pin "12") (pinfunction "I0_12") (pintype "input"))
    )
    (net (code "305") (name "~{SK{slash}RD}") (class "Default")
      (node (ref "E31") (pin "10") (pinfunction "2Y1_10") (pintype "output"))
      (node (ref "E34") (pin "9") (pinfunction "I0_9") (pintype "input"))
    )
    (net (code "306") (name "~{SK{slash}WRT}") (class "Default")
      (node (ref "E31") (pin "6") (pinfunction "1Y1_6") (pintype "output"))
      (node (ref "E33") (pin "13") (pinfunction "I1_13") (pintype "input"))
      (node (ref "E34") (pin "10") (pinfunction "I1_10") (pintype "input"))
      (node (ref "E34") (pin "11") (pinfunction "I2_11") (pintype "input"))
    )
    (net (code "307") (name "~{STATE_ENAB_A}") (class "Default")
      (node (ref "E23") (pin "4") (pinfunction "O_4") (pintype "output"))
      (node (ref "E30") (pin "9") (pinfunction "I1_9") (pintype "input"))
    )
    (net (code "308") (name "~{SYNC_DLY}") (class "Default")
      (node (ref "E37") (pin "2") (pinfunction "D_2") (pintype "input"))
      (node (ref "E38") (pin "12") (pinfunction "~{Q}_12") (pintype "output"))
    )
    (net (code "309") (name "~{WRITE}") (class "Default")
      (node (ref "E41") (pin "8") (pinfunction "~{Q}_8") (pintype "output"))
      (node (ref "E8") (pin "5") (pinfunction "I1_5") (pintype "input"))
    )
    (net (code "310") (name "~{WRT_CLK}") (class "Default")
      (node (ref "E27") (pin "12") (pinfunction "I0_12") (pintype "input"))
      (node (ref "E29") (pin "12") (pinfunction "I1_12") (pintype "input"))
      (node (ref "E36") (pin "11") (pinfunction "I_11") (pintype "input"))
      (node (ref "E39") (pin "8") (pinfunction "O_8") (pintype "output"))
    )
    (net (code "311") (name "~{WRT_CMD}") (class "Default")
      (node (ref "E36") (pin "6") (pinfunction "O_6") (pintype "output"))
      (node (ref "E39") (pin "3") (pinfunction "I0_3") (pintype "input"))
      (node (ref "E43") (pin "1") (pinfunction "A_1") (pintype "input"))
      (node (ref "E51") (pin "9") (pinfunction "I0_9") (pintype "input"))
      (node (ref "F") (pin "V2") (pinfunction "P_V2") (pintype "passive"))
    )
    (net (code "312") (name "~{WRT_LOCK_OUT}") (class "Default")
      (node (ref "E31") (pin "11") (pinfunction "2Y2_11") (pintype "output"))
      (node (ref "E32") (pin "13") (pinfunction "I1_13") (pintype "input"))
      (node (ref "E35") (pin "5") (pinfunction "I_5") (pintype "input"))
    )
    (net (code "313") (name "~{WRT_SYNC_BIT}") (class "Default")
      (node (ref "E34") (pin "13") (pinfunction "I2_13") (pintype "input"))
      (node (ref "E37") (pin "6") (pinfunction "~{Q}_6") (pintype "output"))
    )
  )
)
